# kernel.net
KiCad netlist of a schematic drawn in Altium Designer
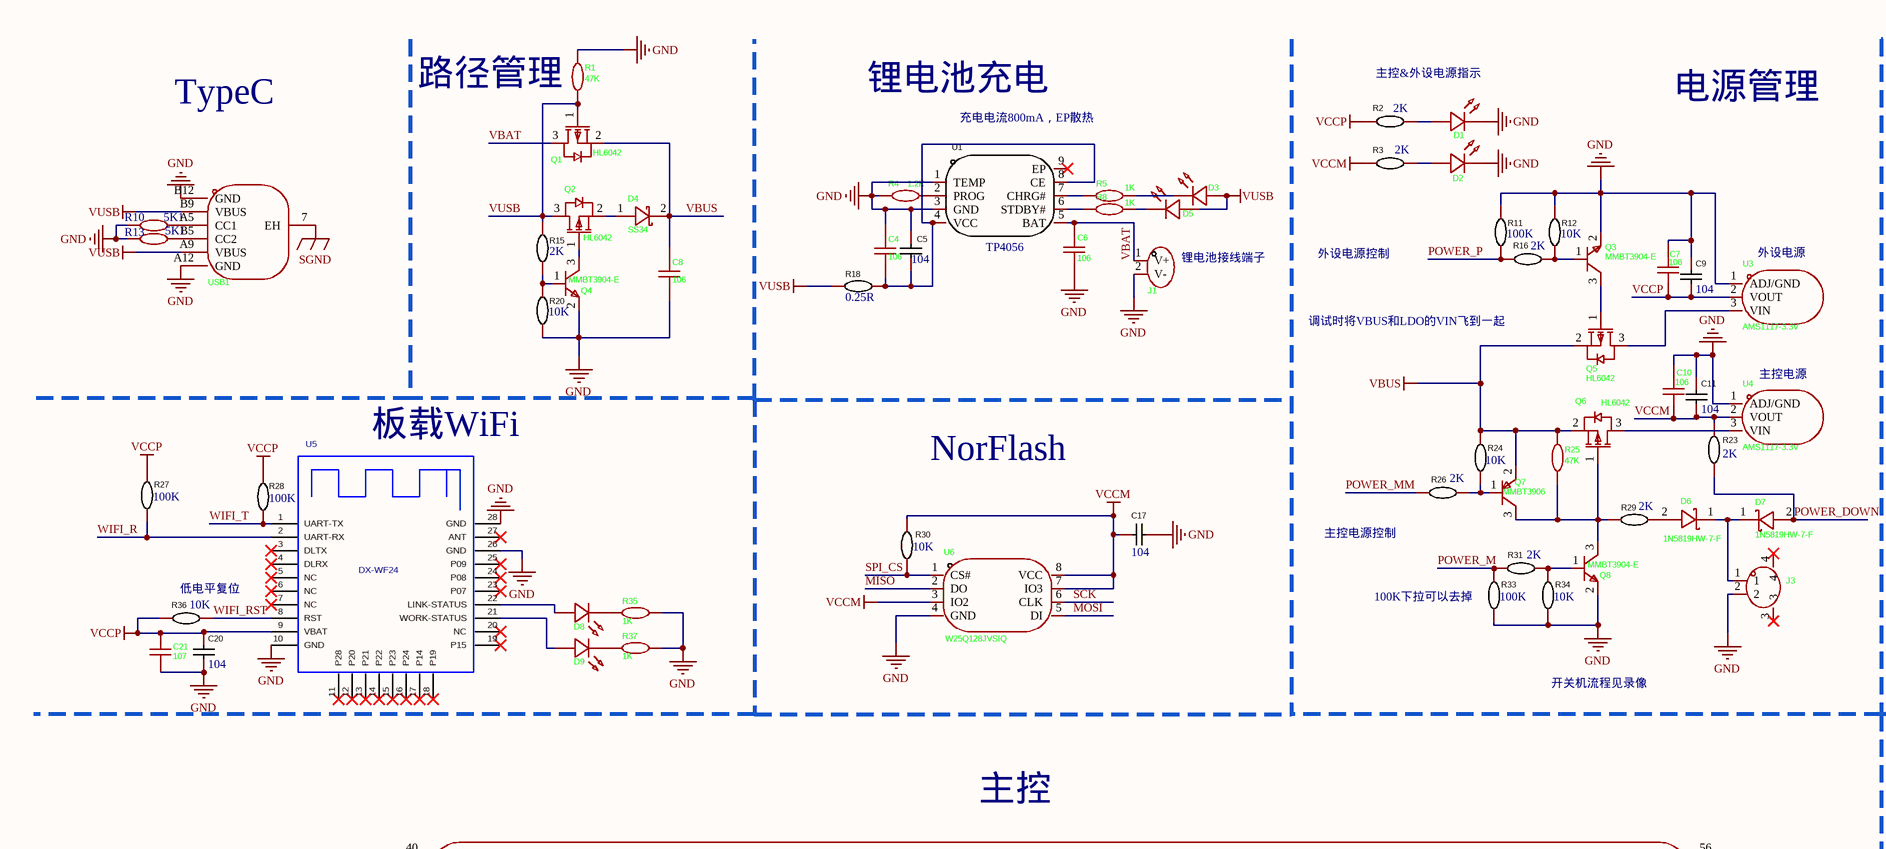
[diagram p0: kernel.SchDoc, top left]
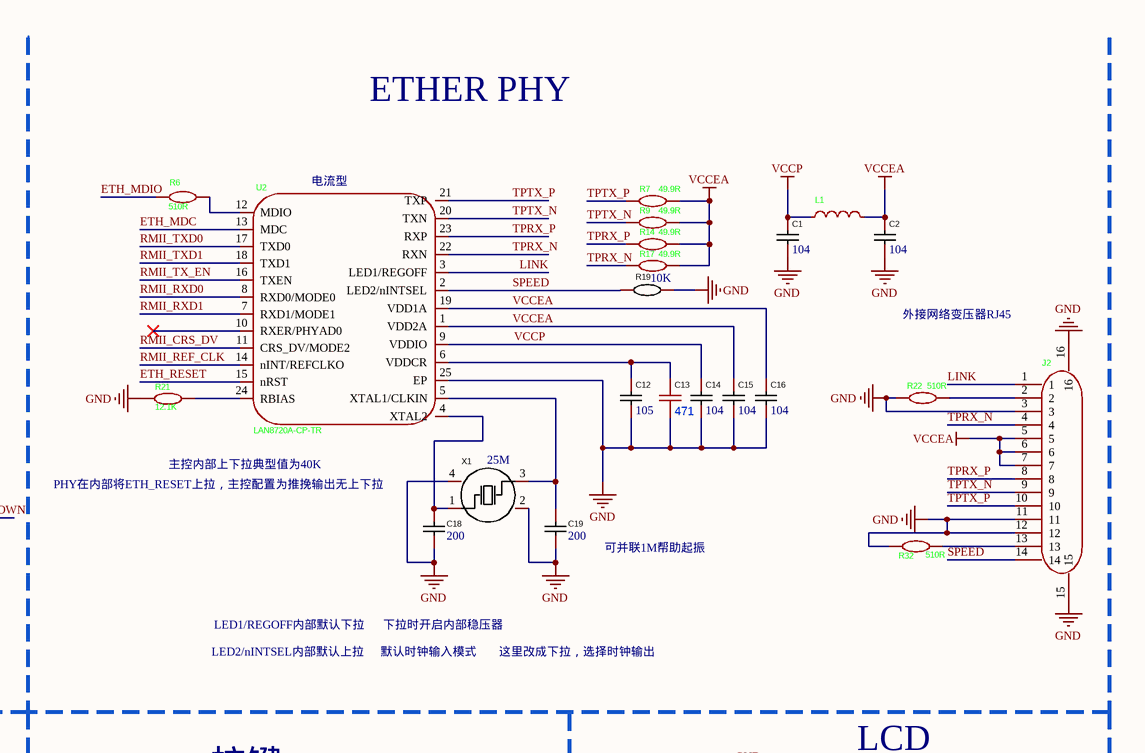
[diagram p1: kernel.SchDoc, top right]
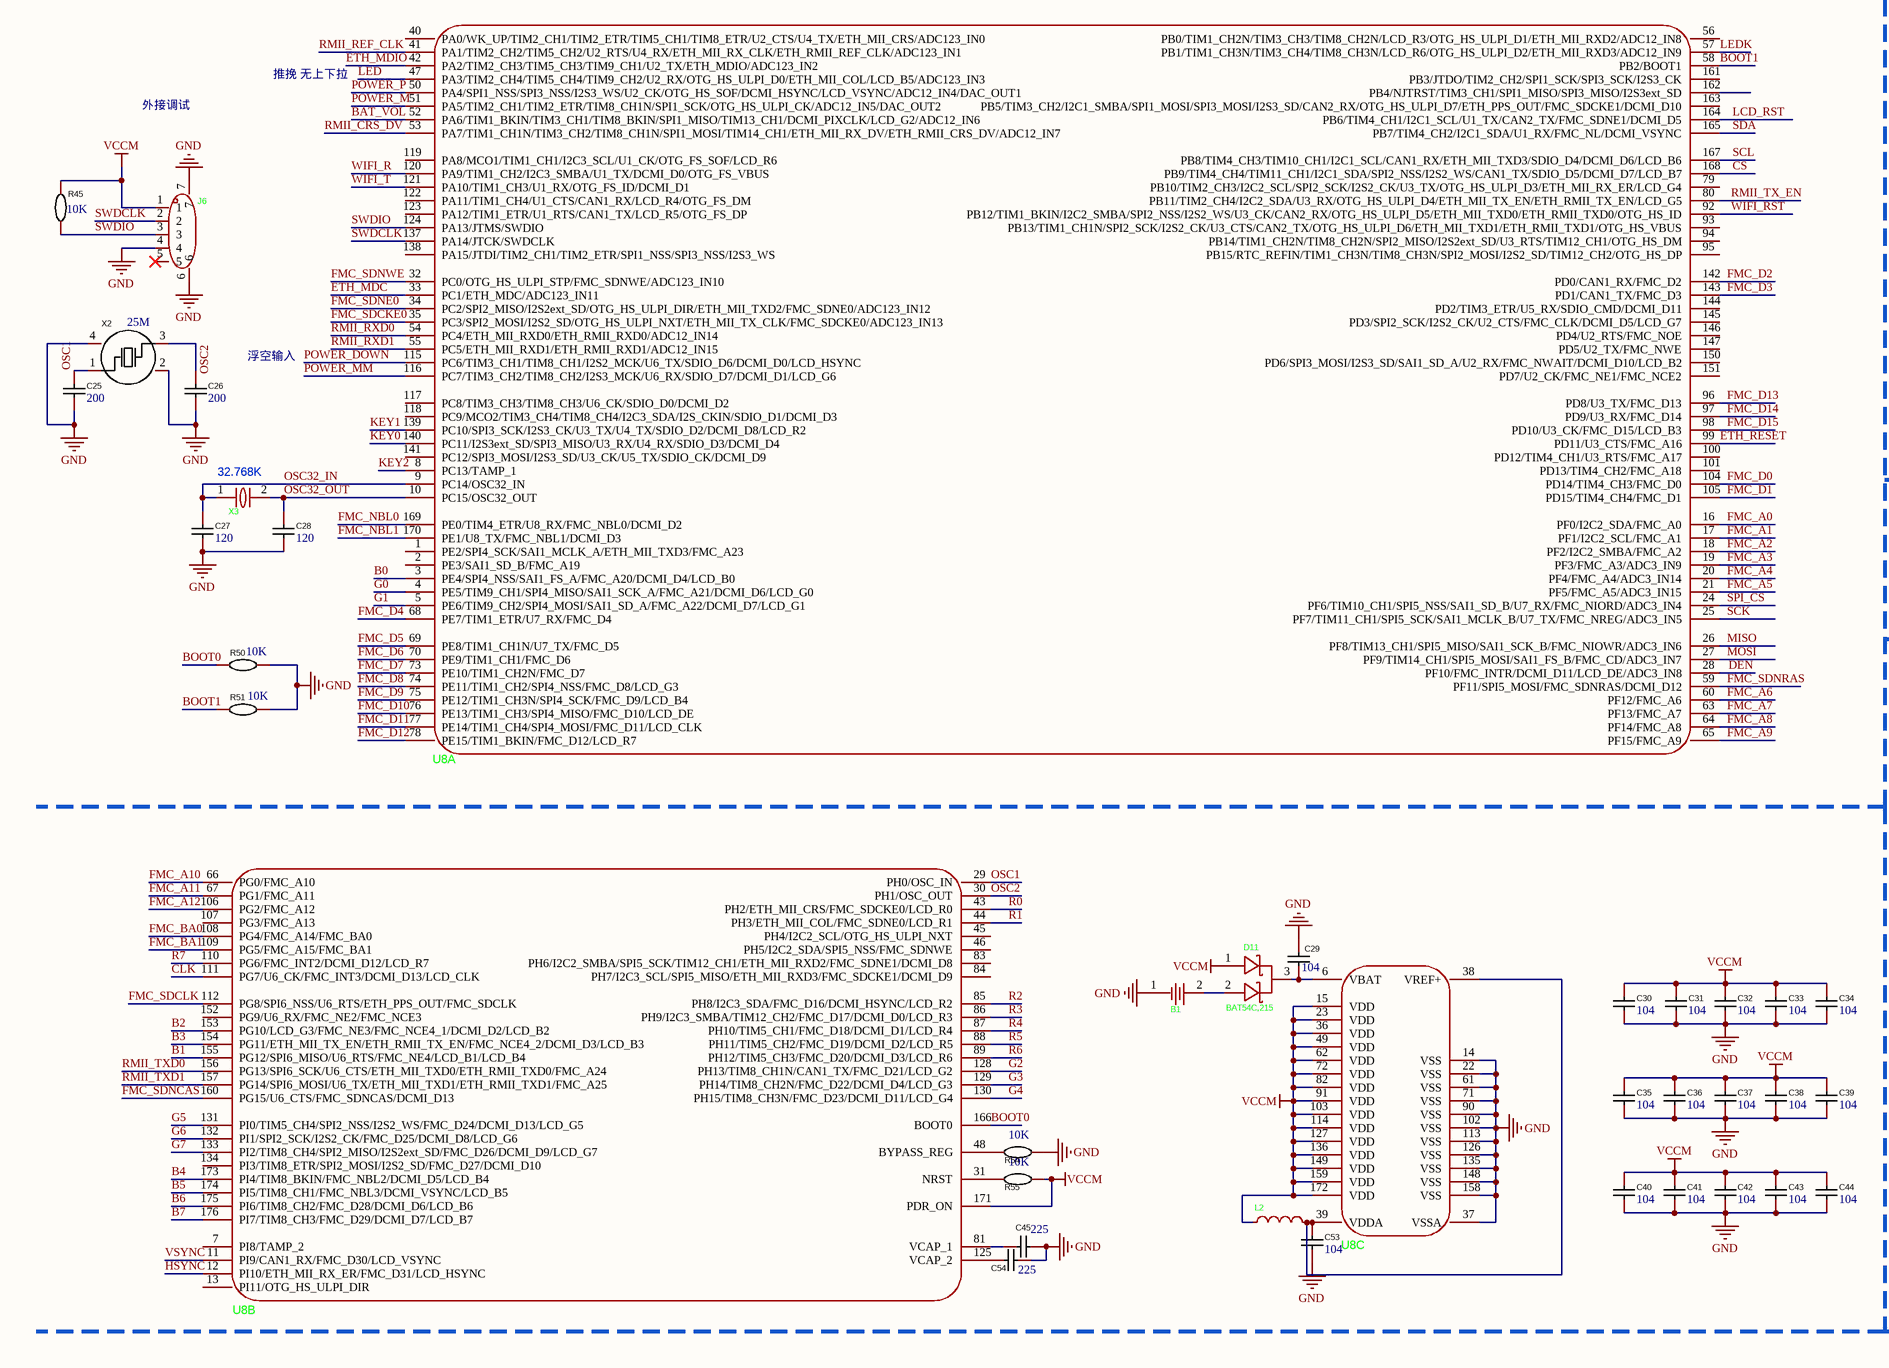
[diagram p2: kernel.SchDoc, bottom left]
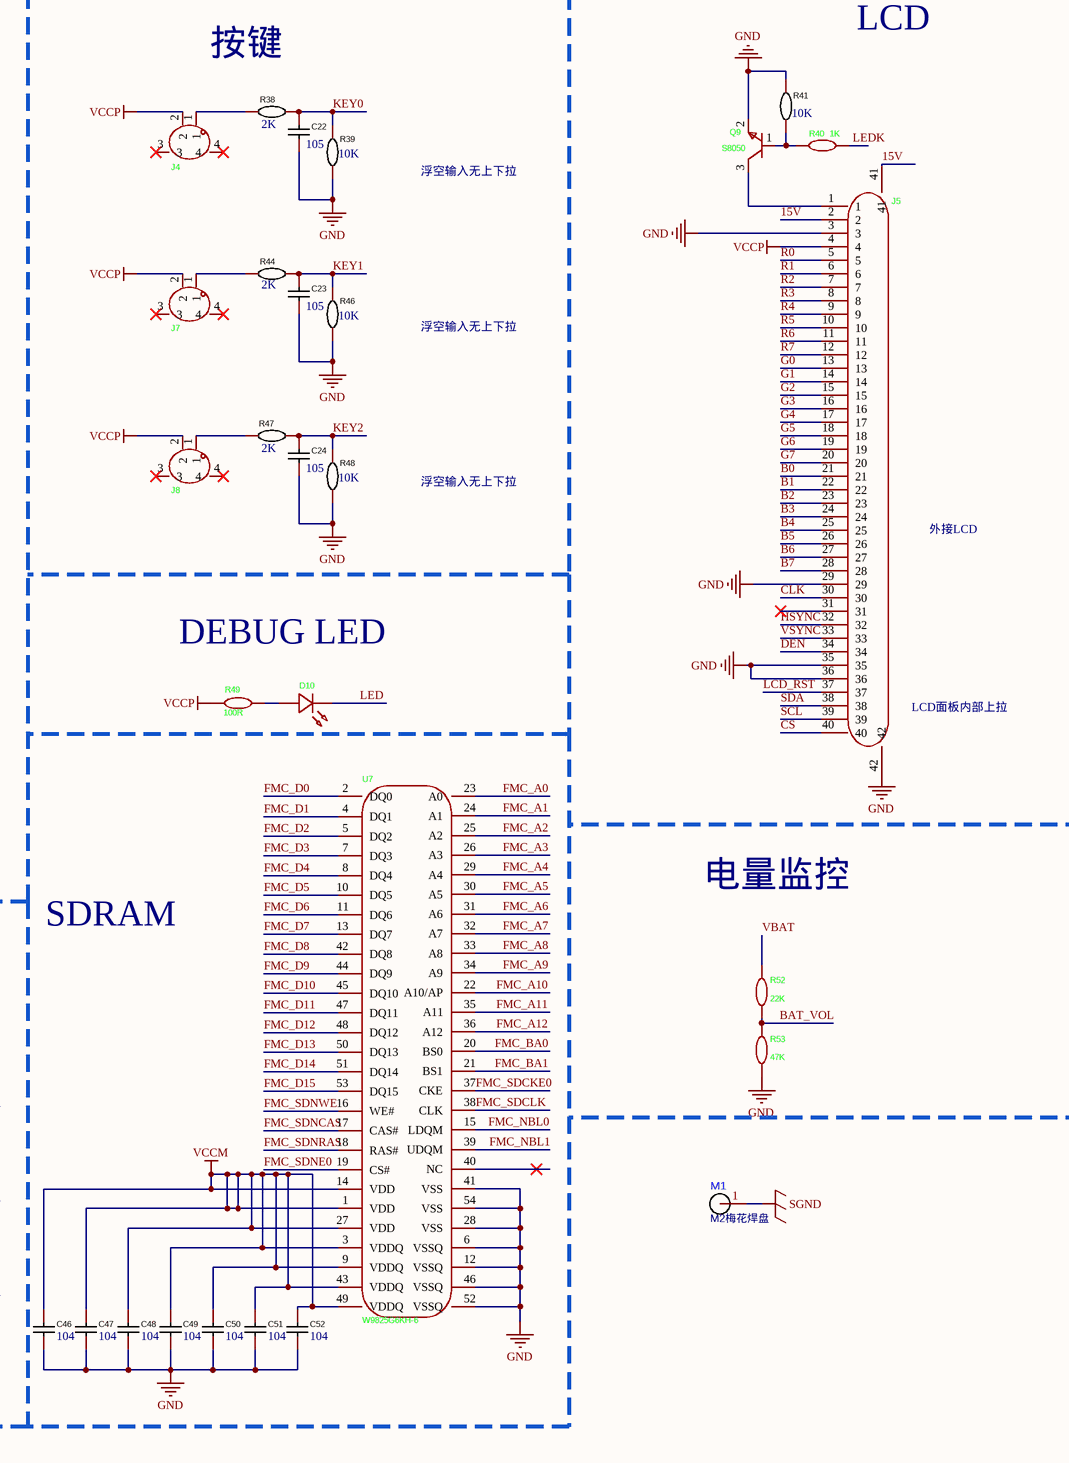
[diagram p3: kernel.SchDoc, bottom right]

(export (version "E")
  (design (tool "Eeschema 10.0.6"))
  (components
    (comp (ref "B1")
      (value "BS-02-A1AJ010")
      (footprint "BAT-TH_BS-02-A1AJ010")
      (description "CR2032电池座")
      (fields (field (name "MANUFACTURER") "MYOUNG(美阳)"))
      (libsource (lib "altium-import") (part "root_0_BS-02-A1AJ010_"))
    )
    (comp (ref "C1")
      (value "104")
      (footprint "0402_C")
      (description "电容100nf")
      (fields (field (name "MANUFACTURER") "FH(风华)") (field (name "MANUFACTURER PART") "0402CG200J500NT"))
      (libsource (lib "altium-import") (part "root_1_0402C_104_"))
    )
    (comp (ref "C2")
      (value "104")
      (footprint "0402_C")
      (description "电容100nf")
      (fields (field (name "MANUFACTURER") "FH(风华)") (field (name "MANUFACTURER PART") "0402CG200J500NT"))
      (libsource (lib "altium-import") (part "root_1_0402C_104_"))
    )
    (comp (ref "C4")
      (value "106")
      (footprint "0603_C")
      (description "电容10uf")
      (fields
        (field (name "MANUFACTURER") "HRE(芯声)")
        (field (name "MANUFACTURER PART") "CGA0603X5R106K100JT")
      )
      (libsource (lib "kernel") (part "CGA0603X5R106K100JT"))
    )
    (comp (ref "C5")
      (value "104")
      (footprint "0402_C")
      (description "电容100nf")
      (fields (field (name "MANUFACTURER") "FH(风华)") (field (name "MANUFACTURER PART") "0402CG200J500NT"))
      (libsource (lib "kernel") (part "0402C_104"))
    )
    (comp (ref "C6")
      (value "106")
      (footprint "0603_C")
      (description "电容10uf")
      (fields
        (field (name "MANUFACTURER") "HRE(芯声)")
        (field (name "MANUFACTURER PART") "CGA0603X5R106K100JT")
      )
      (libsource (lib "kernel") (part "CGA0603X5R106K100JT"))
    )
    (comp (ref "C7")
      (value "106")
      (footprint "0603_C")
      (description "电容10uf")
      (fields
        (field (name "MANUFACTURER") "HRE(芯声)")
        (field (name "MANUFACTURER PART") "CGA0603X5R106K100JT")
      )
      (libsource (lib "kernel") (part "CGA0603X5R106K100JT"))
    )
    (comp (ref "C8")
      (value "106")
      (footprint "0603_C")
      (description "电容10uf")
      (fields
        (field (name "MANUFACTURER") "HRE(芯声)")
        (field (name "MANUFACTURER PART") "CGA0603X5R106K100JT")
      )
      (libsource (lib "kernel") (part "CGA0603X5R106K100JT"))
    )
    (comp (ref "C9")
      (value "104")
      (footprint "0402_C")
      (description "电容100nf")
      (fields (field (name "MANUFACTURER") "FH(风华)") (field (name "MANUFACTURER PART") "0402CG200J500NT"))
      (libsource (lib "altium-import") (part "root_1_0402C_104_"))
    )
    (comp (ref "C10")
      (value "106")
      (footprint "0603_C")
      (description "电容10uf")
      (fields
        (field (name "MANUFACTURER") "HRE(芯声)")
        (field (name "MANUFACTURER PART") "CGA0603X5R106K100JT")
      )
      (libsource (lib "kernel") (part "CGA0603X5R106K100JT"))
    )
    (comp (ref "C11")
      (value "104")
      (footprint "0402_C")
      (description "电容100nf")
      (fields (field (name "MANUFACTURER") "FH(风华)") (field (name "MANUFACTURER PART") "0402CG200J500NT"))
      (libsource (lib "altium-import") (part "root_1_0402C_104_"))
    )
    (comp (ref "C12")
      (value "105")
      (footprint "0402_C")
      (description "电容1uf")
      (fields (field (name "MANUFACTURER") "FH(风华)") (field (name "MANUFACTURER PART") "0402CG200J500NT"))
      (libsource (lib "altium-import") (part "root_1_0402C_105_"))
    )
    (comp (ref "C13")
      (value "471")
      (footprint "0402_C")
      (description "电容470pf")
      (fields (field (name "MANUFACTURER") "FH(风华)") (field (name "MANUFACTURER PART") "0402B471K500NT"))
      (libsource (lib "altium-import") (part "root_1_0402B471K500NT_"))
    )
    (comp (ref "C14")
      (value "104")
      (footprint "0402_C")
      (description "电容100nf")
      (fields (field (name "MANUFACTURER") "FH(风华)") (field (name "MANUFACTURER PART") "0402CG200J500NT"))
      (libsource (lib "altium-import") (part "root_1_0402C_104_"))
    )
    (comp (ref "C15")
      (value "104")
      (footprint "0402_C")
      (description "电容100nf")
      (fields (field (name "MANUFACTURER") "FH(风华)") (field (name "MANUFACTURER PART") "0402CG200J500NT"))
      (libsource (lib "altium-import") (part "root_1_0402C_104_"))
    )
    (comp (ref "C16")
      (value "104")
      (footprint "0402_C")
      (description "电容100nf")
      (fields (field (name "MANUFACTURER") "FH(风华)") (field (name "MANUFACTURER PART") "0402CG200J500NT"))
      (libsource (lib "altium-import") (part "root_1_0402C_104_"))
    )
    (comp (ref "C17")
      (value "104")
      (footprint "0402_C")
      (description "电容100nf")
      (fields (field (name "MANUFACTURER") "FH(风华)") (field (name "MANUFACTURER PART") "0402CG200J500NT"))
      (libsource (lib "altium-import") (part "root_0_0402C_104_"))
    )
    (comp (ref "C18")
      (value "200")
      (footprint "0402_C")
      (description "电容20pf")
      (fields (field (name "MANUFACTURER") "FH(风华)") (field (name "MANUFACTURER PART") "0402CG200J500NT"))
      (libsource (lib "altium-import") (part "root_3_0402C_200_"))
    )
    (comp (ref "C19")
      (value "200")
      (footprint "0402_C")
      (description "电容20pf")
      (fields (field (name "MANUFACTURER") "FH(风华)") (field (name "MANUFACTURER PART") "0402CG200J500NT"))
      (libsource (lib "altium-import") (part "root_3_0402C_200_"))
    )
    (comp (ref "C20")
      (value "104")
      (footprint "0402_C")
      (description "电容100nf")
      (fields (field (name "MANUFACTURER") "FH(风华)") (field (name "MANUFACTURER PART") "0402CG200J500NT"))
      (libsource (lib "altium-import") (part "root_1_0402C_104_"))
    )
    (comp (ref "C21")
      (value "107")
      (footprint "1206_C")
      (description "电容100uf")
      (fields
        (field (name "MANUFACTURER") "SAMSUNG(三星)")
        (field (name "MANUFACTURER PART") "CL31A107MQHNNNE")
      )
      (libsource (lib "Schlib1") (part "CL31A107MQHNNNE"))
    )
    (comp (ref "C22")
      (value "105")
      (footprint "0402_C")
      (description "电容1uf")
      (fields (field (name "MANUFACTURER") "FH(风华)") (field (name "MANUFACTURER PART") "0402CG200J500NT"))
      (libsource (lib "altium-import") (part "root_1_0402C_105_"))
    )
    (comp (ref "C23")
      (value "105")
      (footprint "0402_C")
      (description "电容1uf")
      (fields (field (name "MANUFACTURER") "FH(风华)") (field (name "MANUFACTURER PART") "0402CG200J500NT"))
      (libsource (lib "altium-import") (part "root_1_0402C_105_"))
    )
    (comp (ref "C24")
      (value "105")
      (footprint "0402_C")
      (description "电容1uf")
      (fields (field (name "MANUFACTURER") "FH(风华)") (field (name "MANUFACTURER PART") "0402CG200J500NT"))
      (libsource (lib "altium-import") (part "root_1_0402C_105_"))
    )
    (comp (ref "C25")
      (value "200")
      (footprint "0402_C")
      (description "电容20pf")
      (fields (field (name "MANUFACTURER") "FH(风华)") (field (name "MANUFACTURER PART") "0402CG200J500NT"))
      (libsource (lib "altium-import") (part "root_3_0402C_200_"))
    )
    (comp (ref "C26")
      (value "200")
      (footprint "0402_C")
      (description "电容20pf")
      (fields (field (name "MANUFACTURER") "FH(风华)") (field (name "MANUFACTURER PART") "0402CG200J500NT"))
      (libsource (lib "altium-import") (part "root_3_0402C_200_"))
    )
    (comp (ref "C27")
      (value "120")
      (footprint "0402_C")
      (description "电容12pf")
      (fields (field (name "MANUFACTURER") "FH(风华)") (field (name "MANUFACTURER PART") "0402CG200J500NT"))
      (libsource (lib "altium-import") (part "root_1_0402C_120_"))
    )
    (comp (ref "C28")
      (value "120")
      (footprint "0402_C")
      (description "电容12pf")
      (fields (field (name "MANUFACTURER") "FH(风华)") (field (name "MANUFACTURER PART") "0402CG200J500NT"))
      (libsource (lib "altium-import") (part "root_1_0402C_120_"))
    )
    (comp (ref "C29")
      (value "104")
      (footprint "0402_C")
      (description "电容")
      (fields (field (name "MANUFACTURER") "FH(风华)") (field (name "MANUFACTURER PART") "0402CG200J500NT"))
      (libsource (lib "altium-import") (part "root_1_0402C_"))
    )
    (comp (ref "C30")
      (value "104")
      (footprint "0402_C")
      (description "电容")
      (fields (field (name "MANUFACTURER") "FH(风华)") (field (name "MANUFACTURER PART") "0402CG200J500NT"))
      (libsource (lib "altium-import") (part "root_1_0402C_"))
    )
    (comp (ref "C31")
      (value "104")
      (footprint "0402_C")
      (description "电容")
      (fields (field (name "MANUFACTURER") "FH(风华)") (field (name "MANUFACTURER PART") "0402CG200J500NT"))
      (libsource (lib "altium-import") (part "root_1_0402C_"))
    )
    (comp (ref "C32")
      (value "104")
      (footprint "0402_C")
      (description "电容")
      (fields (field (name "MANUFACTURER") "FH(风华)") (field (name "MANUFACTURER PART") "0402CG200J500NT"))
      (libsource (lib "altium-import") (part "root_1_0402C_"))
    )
    (comp (ref "C33")
      (value "104")
      (footprint "0402_C")
      (description "电容")
      (fields (field (name "MANUFACTURER") "FH(风华)") (field (name "MANUFACTURER PART") "0402CG200J500NT"))
      (libsource (lib "altium-import") (part "root_1_0402C_"))
    )
    (comp (ref "C34")
      (value "104")
      (footprint "0402_C")
      (description "电容")
      (fields (field (name "MANUFACTURER") "FH(风华)") (field (name "MANUFACTURER PART") "0402CG200J500NT"))
      (libsource (lib "altium-import") (part "root_1_0402C_"))
    )
    (comp (ref "C35")
      (value "104")
      (footprint "0402_C")
      (description "电容")
      (fields (field (name "MANUFACTURER") "FH(风华)") (field (name "MANUFACTURER PART") "0402CG200J500NT"))
      (libsource (lib "altium-import") (part "root_1_0402C_"))
    )
    (comp (ref "C36")
      (value "104")
      (footprint "0402_C")
      (description "电容")
      (fields (field (name "MANUFACTURER") "FH(风华)") (field (name "MANUFACTURER PART") "0402CG200J500NT"))
      (libsource (lib "altium-import") (part "root_1_0402C_"))
    )
    (comp (ref "C37")
      (value "104")
      (footprint "0402_C")
      (description "电容")
      (fields (field (name "MANUFACTURER") "FH(风华)") (field (name "MANUFACTURER PART") "0402CG200J500NT"))
      (libsource (lib "altium-import") (part "root_1_0402C_"))
    )
    (comp (ref "C38")
      (value "104")
      (footprint "0402_C")
      (description "电容")
      (fields (field (name "MANUFACTURER") "FH(风华)") (field (name "MANUFACTURER PART") "0402CG200J500NT"))
      (libsource (lib "altium-import") (part "root_1_0402C_"))
    )
    (comp (ref "C39")
      (value "104")
      (footprint "0402_C")
      (description "电容")
      (fields (field (name "MANUFACTURER") "FH(风华)") (field (name "MANUFACTURER PART") "0402CG200J500NT"))
      (libsource (lib "altium-import") (part "root_1_0402C_"))
    )
    (comp (ref "C40")
      (value "104")
      (footprint "0402_C")
      (description "电容")
      (fields (field (name "MANUFACTURER") "FH(风华)") (field (name "MANUFACTURER PART") "0402CG200J500NT"))
      (libsource (lib "altium-import") (part "root_1_0402C_"))
    )
    (comp (ref "C41")
      (value "104")
      (footprint "0402_C")
      (description "电容")
      (fields (field (name "MANUFACTURER") "FH(风华)") (field (name "MANUFACTURER PART") "0402CG200J500NT"))
      (libsource (lib "altium-import") (part "root_1_0402C_"))
    )
    (comp (ref "C42")
      (value "104")
      (footprint "0402_C")
      (description "电容")
      (fields (field (name "MANUFACTURER") "FH(风华)") (field (name "MANUFACTURER PART") "0402CG200J500NT"))
      (libsource (lib "altium-import") (part "root_1_0402C_"))
    )
    (comp (ref "C43")
      (value "104")
      (footprint "0402_C")
      (description "电容")
      (fields (field (name "MANUFACTURER") "FH(风华)") (field (name "MANUFACTURER PART") "0402CG200J500NT"))
      (libsource (lib "altium-import") (part "root_1_0402C_"))
    )
    (comp (ref "C44")
      (value "104")
      (footprint "0402_C")
      (description "电容")
      (fields (field (name "MANUFACTURER") "FH(风华)") (field (name "MANUFACTURER PART") "0402CG200J500NT"))
      (libsource (lib "altium-import") (part "root_1_0402C_"))
    )
    (comp (ref "C45")
      (value "225")
      (footprint "0402_C")
      (description "电容2.2uf")
      (fields (field (name "MANUFACTURER") "FH(风华)") (field (name "MANUFACTURER PART") "0402CG200J500NT"))
      (libsource (lib "kernel") (part "0402C_225"))
    )
    (comp (ref "C46")
      (value "104")
      (footprint "0402_C")
      (description "电容")
      (fields (field (name "MANUFACTURER") "FH(风华)") (field (name "MANUFACTURER PART") "0402CG200J500NT"))
      (libsource (lib "altium-import") (part "root_1_0402C_"))
    )
    (comp (ref "C47")
      (value "104")
      (footprint "0402_C")
      (description "电容")
      (fields (field (name "MANUFACTURER") "FH(风华)") (field (name "MANUFACTURER PART") "0402CG200J500NT"))
      (libsource (lib "altium-import") (part "root_1_0402C_"))
    )
    (comp (ref "C48")
      (value "104")
      (footprint "0402_C")
      (description "电容")
      (fields (field (name "MANUFACTURER") "FH(风华)") (field (name "MANUFACTURER PART") "0402CG200J500NT"))
      (libsource (lib "altium-import") (part "root_1_0402C_"))
    )
    (comp (ref "C49")
      (value "104")
      (footprint "0402_C")
      (description "电容")
      (fields (field (name "MANUFACTURER") "FH(风华)") (field (name "MANUFACTURER PART") "0402CG200J500NT"))
      (libsource (lib "altium-import") (part "root_1_0402C_"))
    )
    (comp (ref "C50")
      (value "104")
      (footprint "0402_C")
      (description "电容")
      (fields (field (name "MANUFACTURER") "FH(风华)") (field (name "MANUFACTURER PART") "0402CG200J500NT"))
      (libsource (lib "altium-import") (part "root_1_0402C_"))
    )
    (comp (ref "C51")
      (value "104")
      (footprint "0402_C")
      (description "电容")
      (fields (field (name "MANUFACTURER") "FH(风华)") (field (name "MANUFACTURER PART") "0402CG200J500NT"))
      (libsource (lib "altium-import") (part "root_1_0402C_"))
    )
    (comp (ref "C52")
      (value "104")
      (footprint "0402_C")
      (description "电容")
      (fields (field (name "MANUFACTURER") "FH(风华)") (field (name "MANUFACTURER PART") "0402CG200J500NT"))
      (libsource (lib "altium-import") (part "root_1_0402C_"))
    )
    (comp (ref "C53")
      (value "104")
      (footprint "0402_C")
      (description "电容")
      (fields (field (name "MANUFACTURER") "FH(风华)") (field (name "MANUFACTURER PART") "0402CG200J500NT"))
      (libsource (lib "altium-import") (part "root_1_0402C_"))
    )
    (comp (ref "C54")
      (value "225")
      (footprint "0402_C")
      (description "电容2.2uf")
      (fields (field (name "MANUFACTURER") "FH(风华)") (field (name "MANUFACTURER PART") "0402CG200J500NT"))
      (libsource (lib "kernel") (part "0402C_225"))
    )
    (comp (ref "D1")
      (value "XL-1005SYGC")
      (footprint "LED-SMD_L1.1-W0.6-FD")
      (description "LED黄绿")
      (fields (field (name "MANUFACTURER") "XINGLIGHT(成兴光)"))
      (libsource (lib "altium-import") (part "root_0_XL-1005SYGC_C22470306_"))
    )
    (comp (ref "D2")
      (value "XL-1005SYGC")
      (footprint "LED-SMD_L1.1-W0.6-FD")
      (description "LED黄绿")
      (fields (field (name "MANUFACTURER") "XINGLIGHT(成兴光)"))
      (libsource (lib "altium-import") (part "root_0_XL-1005SYGC_C22470306_"))
    )
    (comp (ref "D3")
      (value "XL-1005SYGC")
      (footprint "LED-SMD_L1.1-W0.6-FD")
      (description "LED黄绿")
      (fields (field (name "MANUFACTURER") "XINGLIGHT(成兴光)"))
      (libsource (lib "kernel") (part "XL-1005SYGC_C22470306"))
    )
    (comp (ref "D4")
      (value "SS34")
      (footprint "SMA_L4.3-W2.6-LS5.0-FD")
      (fields (field (name "MANUFACTURER") "R+O(宏嘉诚)"))
      (libsource (lib "power") (part "SS34"))
    )
    (comp (ref "D5")
      (value "XL-1005SURC")
      (footprint "LED0402-RD")
      (description "LED红")
      (fields (field (name "MANUFACTURER") "XINGLIGHT(成兴光)"))
      (libsource (lib "kernel") (part "XL-1005SURC_C25503345"))
    )
    (comp (ref "D6")
      (value "1N5819HW-7-F")
      (footprint "SOD-123_L2.7-W1.6-LS3.7-RD")
      (description "肖特基二极管")
      (fields (field (name "MANUFACTURER") "DIODES(美台)"))
      (libsource (lib "power") (part "1N5819HW-7-F"))
    )
    (comp (ref "D7")
      (value "1N5819HW-7-F")
      (footprint "SOD-123_L2.7-W1.6-LS3.7-RD")
      (description "肖特基二极管")
      (fields (field (name "MANUFACTURER") "DIODES(美台)"))
      (libsource (lib "power") (part "1N5819HW-7-F"))
    )
    (comp (ref "D8")
      (value "XL-1005SURC")
      (footprint "LED0402-RD")
      (description "LED红")
      (fields (field (name "MANUFACTURER") "XINGLIGHT(成兴光)"))
      (libsource (lib "Schlib1") (part "XL-1005SURC_C25503345"))
    )
    (comp (ref "D9")
      (value "XL-1005SURC")
      (footprint "LED0402-RD")
      (description "LED红")
      (fields (field (name "MANUFACTURER") "XINGLIGHT(成兴光)"))
      (libsource (lib "Schlib1") (part "XL-1005SURC_C25503345"))
    )
    (comp (ref "D10")
      (value "XL-1005UOC")
      (footprint "LED0402-RD_ORANGE")
      (description "LED橙")
      (fields (field (name "MANUFACTURER") "XINGLIGHT(成兴光)"))
      (libsource (lib "altium-import") (part "root_2_XL-1005UOC_"))
    )
    (comp (ref "D11")
      (value "BAT54C,215")
      (footprint "SOT-23-3_L2.9-W1.6-P1.90-LS2.8-BR")
      (description "共阴二极管")
      (fields (field (name "MANUFACTURER") "Nexperia(安世)"))
      (libsource (lib "altium-import") (part "root_0_BAT54C,215_"))
    )
    (comp (ref "J1")
      (value "ZX-XH2.54-2PZZ")
      (footprint "CONN-TH_2P-P2.50_HX25003-2A")
      (fields (field (name "MANUFACTURER") "Megastar(兆星)"))
      (libsource (lib "power") (part "ZX-XH2.54-2PZZ"))
    )
    (comp (ref "J2")
      (value "AFC01-S14FCA-00")
      (footprint "FPC-SMD_AFC01-S14FCA-00")
      (description "FPC")
      (fields (field (name "MANUFACTURER") "JS(钜硕电子)"))
      (libsource (lib "altium-import") (part "root_0_AFC01-S14FCA-00_"))
    )
    (comp (ref "J3")
      (value "WAFER-SH1.0-2PWB")
      (footprint "CONN-SMD_2P-P1.00_XUNPU_WAFER-SH1.0-2PWB")
      (description "按键连接器")
      (fields (field (name "MANUFACTURER") "XUNPU(讯普)"))
      (libsource (lib "kernel") (part "WAFER-SH1.0-2PWB"))
    )
    (comp (ref "J4")
      (value "WAFER-SH1.0-2PWB")
      (footprint "CONN-SMD_2P-P1.00_XUNPU_WAFER-SH1.0-2PWB")
      (description "按键连接器")
      (fields (field (name "MANUFACTURER") "XUNPU(讯普)"))
      (libsource (lib "kernel") (part "WAFER-SH1.0-2PWB"))
    )
    (comp (ref "J5")
      (value "AFC01-S40FCA-00")
      (footprint "FPC-SMD_AFC01-S40FCA-00")
      (description "FPC")
      (fields (field (name "MANUFACTURER") "JS(钜硕电子)"))
      (libsource (lib "Schlib1") (part "AFC01-S40FCA-00"))
    )
    (comp (ref "J6")
      (value "AFC01-S05FCA-00")
      (footprint "FPC-SMD_AFC01-S05FCA-00")
      (description "DEBUG")
      (fields (field (name "MANUFACTURER") "JS(钜硕电子)"))
      (libsource (lib "altium-import") (part "root_0_AFC01-S05FCA-00_"))
    )
    (comp (ref "J7")
      (value "WAFER-SH1.0-2PWB")
      (footprint "CONN-SMD_2P-P1.00_XUNPU_WAFER-SH1.0-2PWB")
      (description "按键连接器")
      (fields (field (name "MANUFACTURER") "XUNPU(讯普)"))
      (libsource (lib "kernel") (part "WAFER-SH1.0-2PWB"))
    )
    (comp (ref "J8")
      (value "WAFER-SH1.0-2PWB")
      (footprint "CONN-SMD_2P-P1.00_XUNPU_WAFER-SH1.0-2PWB")
      (description "按键连接器")
      (fields (field (name "MANUFACTURER") "XUNPU(讯普)"))
      (libsource (lib "kernel") (part "WAFER-SH1.0-2PWB"))
    )
    (comp (ref "L1")
      (value "BLM21PG221SN1D")
      (footprint "0805_L")
      (description "磁珠")
      (fields (field (name "MANUFACTURER") "muRata(村田)") (field (name "TOLERANCE") "±25%"))
      (libsource (lib "altium-import") (part "root_0_BLM21PG221SN1D_"))
    )
    (comp (ref "L2")
      (value "BLM15AG100SN1D")
      (footprint "0402_L")
      (fields (field (name "MANUFACTURER") "muRata(村田)"))
      (libsource (lib "kernel") (part "BLM15AG100SN1D"))
    )
    (comp (ref "M1")
      (value "M2梅花焊盘")
      (footprint "PCBComponent_1 - duplicate")
      (libsource (lib "kernel") (part "M2梅花焊盘"))
    )
    (comp (ref "Q1")
      (value "HL6042")
      (footprint "SOT-23-3_L2.9-W1.4-P1.90-LS2.5-BR")
      (fields (field (name "MANUFACTURER") "R+O(宏嘉诚)"))
      (libsource (lib "power") (part "HL6042"))
    )
    (comp (ref "Q2")
      (value "HL6042")
      (footprint "SOT-23-3_L2.9-W1.4-P1.90-LS2.5-BR")
      (fields (field (name "MANUFACTURER") "R+O(宏嘉诚)"))
      (libsource (lib "power") (part "HL6042"))
    )
    (comp (ref "Q3")
      (value "MMBT3904-E")
      (footprint "SOT-23-3_L2.9-W1.4-P1.90-LS2.5-BR")
      (description "NPN")
      (fields (field (name "MANUFACTURER") "MDD(辰达半导体)"))
      (libsource (lib "power") (part "MMBT3904-E"))
    )
    (comp (ref "Q4")
      (value "MMBT3904-E")
      (footprint "SOT-23-3_L2.9-W1.4-P1.90-LS2.5-BR")
      (description "NPN")
      (fields (field (name "MANUFACTURER") "MDD(辰达半导体)"))
      (libsource (lib "power") (part "MMBT3904-E"))
    )
    (comp (ref "Q5")
      (value "HL6042")
      (footprint "SOT-23-3_L2.9-W1.4-P1.90-LS2.5-BR")
      (fields (field (name "MANUFACTURER") "R+O(宏嘉诚)"))
      (libsource (lib "power") (part "HL6042"))
    )
    (comp (ref "Q6")
      (value "HL6042")
      (footprint "SOT-23-3_L2.9-W1.4-P1.90-LS2.5-BR")
      (fields (field (name "MANUFACTURER") "R+O(宏嘉诚)"))
      (libsource (lib "power") (part "HL6042"))
    )
    (comp (ref "Q7")
      (value "MMBT3906")
      (footprint "SOT-23-3_L2.9-W1.3-P1.90-LS2.4-BR")
      (description "PNP")
      (fields (field (name "MANUFACTURER") "MDD(辰达半导体)"))
      (libsource (lib "power") (part "MMBT3906_C364311"))
    )
    (comp (ref "Q8")
      (value "MMBT3904-E")
      (footprint "SOT-23-3_L2.9-W1.4-P1.90-LS2.5-BR")
      (description "NPN")
      (fields (field (name "MANUFACTURER") "MDD(辰达半导体)"))
      (libsource (lib "power") (part "MMBT3904-E"))
    )
    (comp (ref "Q9")
      (value "S8050")
      (footprint "SOT-23-3_L3.0-W1.7-P0.95-LS2.9-BR")
      (description "NPN")
      (fields (field (name "MANUFACTURER") "MDD(辰达半导体)"))
      (libsource (lib "kernel") (part "S8050_C364312"))
    )
    (comp (ref "R1")
      (value "47K")
      (footprint "0402_R")
      (description "电阻47K")
      (fields
        (field (name "MANUFACTURER") "UNI-ROYAL(厚声)")
        (field (name "MANUFACTURER PART") "0402WGF4702TCE")
      )
      (libsource (lib "kernel") (part "0402WGF4702TCE"))
    )
    (comp (ref "R2")
      (value "2K")
      (footprint "0402_R")
      (description "电阻2K")
      (fields
        (field (name "MANUFACTURER") "UNI-ROYAL(厚声)")
        (field (name "MANUFACTURER PART") "0402WGF1002TCE")
      )
      (libsource (lib "kernel") (part "0402WGF2001TCE"))
    )
    (comp (ref "R3")
      (value "2K")
      (footprint "0402_R")
      (description "电阻2K")
      (fields
        (field (name "MANUFACTURER") "UNI-ROYAL(厚声)")
        (field (name "MANUFACTURER PART") "0402WGF1002TCE")
      )
      (libsource (lib "kernel") (part "0402WGF2001TCE"))
    )
    (comp (ref "R4")
      (value "1.2K")
      (footprint "0603_R")
      (description "电阻1.2K")
      (fields
        (field (name "MANUFACTURER") "UNI-ROYAL(厚声)")
        (field (name "MANUFACTURER PART") "0603WAF1201T5E")
      )
      (libsource (lib "kernel") (part "0603WAF1201T5E"))
    )
    (comp (ref "R5")
      (value "1K")
      (footprint "0402_R")
      (description "电阻1K")
      (fields
        (field (name "MANUFACTURER") "UNI-ROYAL(厚声)")
        (field (name "MANUFACTURER PART") "0402WGF1001TCE")
      )
      (libsource (lib "kernel") (part "0402WGF1001TCE"))
    )
    (comp (ref "R6")
      (value "510R")
      (footprint "0603_R")
      (description "电阻510R")
      (fields
        (field (name "MANUFACTURER") "UNI-ROYAL(厚声)")
        (field (name "MANUFACTURER PART") "0603WAF5100T5E")
      )
      (libsource (lib "altium-import") (part "root_0_0603WAF5100T5E_"))
    )
    (comp (ref "R7")
      (value "49.9R")
      (footprint "0603_R")
      (description "电阻49.9R")
      (fields
        (field (name "MANUFACTURER") "UNI-ROYAL(厚声)")
        (field (name "MANUFACTURER PART") "0603WAF499JT5E")
      )
      (libsource (lib "altium-import") (part "root_0_0603WAF499JT5E_"))
    )
    (comp (ref "R8")
      (value "1K")
      (footprint "0402_R")
      (description "电阻1K")
      (fields
        (field (name "MANUFACTURER") "UNI-ROYAL(厚声)")
        (field (name "MANUFACTURER PART") "0402WGF1001TCE")
      )
      (libsource (lib "kernel") (part "0402WGF1001TCE"))
    )
    (comp (ref "R9")
      (value "49.9R")
      (footprint "0603_R")
      (description "电阻49.9R")
      (fields
        (field (name "MANUFACTURER") "UNI-ROYAL(厚声)")
        (field (name "MANUFACTURER PART") "0603WAF499JT5E")
      )
      (libsource (lib "altium-import") (part "root_0_0603WAF499JT5E_"))
    )
    (comp (ref "R10")
      (value "5K1")
      (footprint "0402_R")
      (description "电阻5.1K")
      (libsource (lib "kernel") (part "0402WGF5101TCE"))
    )
    (comp (ref "R11")
      (value "100K")
      (footprint "0402_R")
      (description "电阻100K")
      (fields
        (field (name "MANUFACTURER") "UNI-ROYAL(厚声)")
        (field (name "MANUFACTURER PART") "0402WGF1002TCE")
      )
      (libsource (lib "kernel") (part "0402WGF1003TCE"))
    )
    (comp (ref "R12")
      (value "10K")
      (footprint "0402_R")
      (description "电阻10K")
      (fields
        (field (name "MANUFACTURER") "UNI-ROYAL(厚声)")
        (field (name "MANUFACTURER PART") "0402WGF1002TCE")
      )
      (libsource (lib "altium-import") (part "root_1_0402WGF1002TCE_"))
    )
    (comp (ref "R13")
      (value "5K1")
      (footprint "0402_R")
      (description "电阻5.1K")
      (libsource (lib "kernel") (part "0402WGF5101TCE"))
    )
    (comp (ref "R14")
      (value "49.9R")
      (footprint "0603_R")
      (description "电阻49.9R")
      (fields
        (field (name "MANUFACTURER") "UNI-ROYAL(厚声)")
        (field (name "MANUFACTURER PART") "0603WAF499JT5E")
      )
      (libsource (lib "altium-import") (part "root_0_0603WAF499JT5E_"))
    )
    (comp (ref "R15")
      (value "2K")
      (footprint "0402_R")
      (description "电阻2K")
      (fields
        (field (name "MANUFACTURER") "UNI-ROYAL(厚声)")
        (field (name "MANUFACTURER PART") "0402WGF1002TCE")
      )
      (libsource (lib "kernel") (part "0402WGF2001TCE"))
    )
    (comp (ref "R16")
      (value "2K")
      (footprint "0402_R")
      (description "电阻2K")
      (fields
        (field (name "MANUFACTURER") "UNI-ROYAL(厚声)")
        (field (name "MANUFACTURER PART") "0402WGF1002TCE")
      )
      (libsource (lib "kernel") (part "0402WGF2001TCE"))
    )
    (comp (ref "R17")
      (value "49.9R")
      (footprint "0603_R")
      (description "电阻49.9R")
      (fields
        (field (name "MANUFACTURER") "UNI-ROYAL(厚声)")
        (field (name "MANUFACTURER PART") "0603WAF499JT5E")
      )
      (libsource (lib "altium-import") (part "root_0_0603WAF499JT5E_"))
    )
    (comp (ref "R18")
      (value "0.25R")
      (footprint "1206_R")
      (description "res")
      (fields
        (field (name "MANUFACTURER") "UNI-ROYAL(厚声)")
        (field (name "MANUFACTURER PART") "0402WGF1002TCE")
      )
      (libsource (lib "Schlib1") (part "0402WGF1002TCE"))
    )
    (comp (ref "R19")
      (value "10K")
      (footprint "0402_R")
      (description "电阻10K")
      (fields
        (field (name "MANUFACTURER") "UNI-ROYAL(厚声)")
        (field (name "MANUFACTURER PART") "0402WGF1002TCE")
      )
      (libsource (lib "altium-import") (part "root_0_0402WGF1002TCE_"))
    )
    (comp (ref "R20")
      (value "10K")
      (footprint "0402_R")
      (description "电阻10K")
      (fields
        (field (name "MANUFACTURER") "UNI-ROYAL(厚声)")
        (field (name "MANUFACTURER PART") "0402WGF1002TCE")
      )
      (libsource (lib "altium-import") (part "root_1_0402WGF1002TCE_"))
    )
    (comp (ref "R21")
      (value "12.1K")
      (footprint "0603_R")
      (description "电阻12.1K")
      (fields
        (field (name "MANUFACTURER") "UNI-ROYAL(厚声)")
        (field (name "MANUFACTURER PART") "0603WAF1212T5E")
      )
      (libsource (lib "altium-import") (part "root_0_0603WAF1212T5E_"))
    )
    (comp (ref "R22")
      (value "510R")
      (footprint "0603_R")
      (description "电阻510R")
      (fields
        (field (name "MANUFACTURER") "UNI-ROYAL(厚声)")
        (field (name "MANUFACTURER PART") "0603WAF5100T5E")
      )
      (libsource (lib "altium-import") (part "root_0_0603WAF5100T5E_"))
    )
    (comp (ref "R23")
      (value "2K")
      (footprint "0402_R")
      (description "电阻2K")
      (fields
        (field (name "MANUFACTURER") "UNI-ROYAL(厚声)")
        (field (name "MANUFACTURER PART") "0402WGF1002TCE")
      )
      (libsource (lib "kernel") (part "0402WGF2001TCE"))
    )
    (comp (ref "R24")
      (value "10K")
      (footprint "0402_R")
      (description "电阻10K")
      (fields
        (field (name "MANUFACTURER") "UNI-ROYAL(厚声)")
        (field (name "MANUFACTURER PART") "0402WGF1002TCE")
      )
      (libsource (lib "altium-import") (part "root_1_0402WGF1002TCE_"))
    )
    (comp (ref "R25")
      (value "47K")
      (footprint "0402_R")
      (description "电阻47K")
      (fields
        (field (name "MANUFACTURER") "UNI-ROYAL(厚声)")
        (field (name "MANUFACTURER PART") "0402WGF4702TCE")
      )
      (libsource (lib "kernel") (part "0402WGF4702TCE"))
    )
    (comp (ref "R26")
      (value "2K")
      (footprint "0402_R")
      (description "电阻2K")
      (fields
        (field (name "MANUFACTURER") "UNI-ROYAL(厚声)")
        (field (name "MANUFACTURER PART") "0402WGF1002TCE")
      )
      (libsource (lib "kernel") (part "0402WGF2001TCE"))
    )
    (comp (ref "R27")
      (value "100K")
      (footprint "0402_R")
      (description "电阻100K")
      (fields
        (field (name "MANUFACTURER") "UNI-ROYAL(厚声)")
        (field (name "MANUFACTURER PART") "0402WGF1002TCE")
      )
      (libsource (lib "Schlib1") (part "0402WGF1003TCE"))
    )
    (comp (ref "R28")
      (value "100K")
      (footprint "0402_R")
      (description "电阻100K")
      (fields
        (field (name "MANUFACTURER") "UNI-ROYAL(厚声)")
        (field (name "MANUFACTURER PART") "0402WGF1002TCE")
      )
      (libsource (lib "Schlib1") (part "0402WGF1003TCE"))
    )
    (comp (ref "R29")
      (value "2K")
      (footprint "0402_R")
      (description "电阻2K")
      (fields
        (field (name "MANUFACTURER") "UNI-ROYAL(厚声)")
        (field (name "MANUFACTURER PART") "0402WGF1002TCE")
      )
      (libsource (lib "kernel") (part "0402WGF2001TCE"))
    )
    (comp (ref "R30")
      (value "10K")
      (footprint "0402_R")
      (description "电阻10K")
      (fields
        (field (name "MANUFACTURER") "UNI-ROYAL(厚声)")
        (field (name "MANUFACTURER PART") "0402WGF1002TCE")
      )
      (libsource (lib "altium-import") (part "root_1_0402WGF1002TCE_"))
    )
    (comp (ref "R31")
      (value "2K")
      (footprint "0402_R")
      (description "电阻2K")
      (fields
        (field (name "MANUFACTURER") "UNI-ROYAL(厚声)")
        (field (name "MANUFACTURER PART") "0402WGF1002TCE")
      )
      (libsource (lib "kernel") (part "0402WGF2001TCE"))
    )
    (comp (ref "R32")
      (value "510R")
      (footprint "0603_R")
      (description "电阻510R")
      (fields
        (field (name "MANUFACTURER") "UNI-ROYAL(厚声)")
        (field (name "MANUFACTURER PART") "0603WAF5100T5E")
      )
      (libsource (lib "altium-import") (part "root_0_0603WAF5100T5E_"))
    )
    (comp (ref "R33")
      (value "100K")
      (footprint "0402_R")
      (description "电阻100K")
      (fields
        (field (name "MANUFACTURER") "UNI-ROYAL(厚声)")
        (field (name "MANUFACTURER PART") "0402WGF1002TCE")
      )
      (libsource (lib "kernel") (part "0402WGF1003TCE"))
    )
    (comp (ref "R34")
      (value "10K")
      (footprint "0402_R")
      (description "电阻10K")
      (fields
        (field (name "MANUFACTURER") "UNI-ROYAL(厚声)")
        (field (name "MANUFACTURER PART") "0402WGF1002TCE")
      )
      (libsource (lib "altium-import") (part "root_1_0402WGF1002TCE_"))
    )
    (comp (ref "R35")
      (value "1K")
      (footprint "0402_R")
      (description "电阻1K")
      (fields
        (field (name "MANUFACTURER") "UNI-ROYAL(厚声)")
        (field (name "MANUFACTURER PART") "0402WGF1001TCE")
      )
      (libsource (lib "Schlib1") (part "0402WGF1001TCE"))
    )
    (comp (ref "R36")
      (value "10K")
      (footprint "0402_R")
      (description "电阻10K")
      (fields
        (field (name "MANUFACTURER") "UNI-ROYAL(厚声)")
        (field (name "MANUFACTURER PART") "0402WGF1002TCE")
      )
      (libsource (lib "altium-import") (part "root_2_0402WGF1002TCE_"))
    )
    (comp (ref "R37")
      (value "1K")
      (footprint "0402_R")
      (description "电阻1K")
      (fields
        (field (name "MANUFACTURER") "UNI-ROYAL(厚声)")
        (field (name "MANUFACTURER PART") "0402WGF1001TCE")
      )
      (libsource (lib "Schlib1") (part "0402WGF1001TCE"))
    )
    (comp (ref "R38")
      (value "2K")
      (footprint "0402_R")
      (description "电阻2K")
      (fields
        (field (name "MANUFACTURER") "UNI-ROYAL(厚声)")
        (field (name "MANUFACTURER PART") "0402WGF1002TCE")
      )
      (libsource (lib "altium-import") (part "root_0_0402WGF2001TCE_"))
    )
    (comp (ref "R39")
      (value "10K")
      (footprint "0402_R")
      (description "电阻10K")
      (fields
        (field (name "MANUFACTURER") "UNI-ROYAL(厚声)")
        (field (name "MANUFACTURER PART") "0402WGF1002TCE")
      )
      (libsource (lib "altium-import") (part "root_3_0402WGF1002TCE_"))
    )
    (comp (ref "R40")
      (value "1K")
      (footprint "0402_R")
      (description "电阻1K")
      (fields
        (field (name "MANUFACTURER") "UNI-ROYAL(厚声)")
        (field (name "MANUFACTURER PART") "0402WGF1001TCE")
      )
      (libsource (lib "kernel") (part "0402WGF1001TCE"))
    )
    (comp (ref "R41")
      (value "10K")
      (footprint "0402_R")
      (description "电阻10K")
      (fields
        (field (name "MANUFACTURER") "UNI-ROYAL(厚声)")
        (field (name "MANUFACTURER PART") "0402WGF1002TCE")
      )
      (libsource (lib "kernel") (part "0402WGF1002TCE"))
    )
    (comp (ref "R44")
      (value "2K")
      (footprint "0402_R")
      (description "电阻2K")
      (fields
        (field (name "MANUFACTURER") "UNI-ROYAL(厚声)")
        (field (name "MANUFACTURER PART") "0402WGF1002TCE")
      )
      (libsource (lib "altium-import") (part "root_0_0402WGF2001TCE_"))
    )
    (comp (ref "R45")
      (value "10K")
      (footprint "0402_R")
      (description "电阻10K")
      (fields
        (field (name "MANUFACTURER") "UNI-ROYAL(厚声)")
        (field (name "MANUFACTURER PART") "0402WGF1002TCE")
      )
      (libsource (lib "altium-import") (part "root_3_0402WGF1002TCE_"))
    )
    (comp (ref "R46")
      (value "10K")
      (footprint "0402_R")
      (description "电阻10K")
      (fields
        (field (name "MANUFACTURER") "UNI-ROYAL(厚声)")
        (field (name "MANUFACTURER PART") "0402WGF1002TCE")
      )
      (libsource (lib "altium-import") (part "root_3_0402WGF1002TCE_"))
    )
    (comp (ref "R47")
      (value "2K")
      (footprint "0402_R")
      (description "电阻2K")
      (fields
        (field (name "MANUFACTURER") "UNI-ROYAL(厚声)")
        (field (name "MANUFACTURER PART") "0402WGF1002TCE")
      )
      (libsource (lib "altium-import") (part "root_0_0402WGF2001TCE_"))
    )
    (comp (ref "R48")
      (value "10K")
      (footprint "0402_R")
      (description "电阻10K")
      (fields
        (field (name "MANUFACTURER") "UNI-ROYAL(厚声)")
        (field (name "MANUFACTURER PART") "0402WGF1002TCE")
      )
      (libsource (lib "altium-import") (part "root_3_0402WGF1002TCE_"))
    )
    (comp (ref "R49")
      (value "100R")
      (footprint "0402_R")
      (description "电阻100R")
      (fields
        (field (name "MANUFACTURER") "UNI-ROYAL(厚声)")
        (field (name "MANUFACTURER PART") "0402WGF1000TCE")
      )
      (libsource (lib "altium-import") (part "root_0_0402WGF1000TCE_"))
    )
    (comp (ref "R50")
      (value "10K")
      (footprint "0402_R")
      (description "电阻10K")
      (fields
        (field (name "MANUFACTURER") "UNI-ROYAL(厚声)")
        (field (name "MANUFACTURER PART") "0402WGF1002TCE")
      )
      (libsource (lib "altium-import") (part "root_0_0402WGF1002TCE_"))
    )
    (comp (ref "R51")
      (value "10K")
      (footprint "0402_R")
      (description "电阻10K")
      (fields
        (field (name "MANUFACTURER") "UNI-ROYAL(厚声)")
        (field (name "MANUFACTURER PART") "0402WGF1002TCE")
      )
      (libsource (lib "altium-import") (part "root_0_0402WGF1002TCE_"))
    )
    (comp (ref "R52")
      (value "22K")
      (footprint "0402_R")
      (description "电阻47K")
      (fields
        (field (name "MANUFACTURER") "UNI-ROYAL(厚声)")
        (field (name "MANUFACTURER PART") "0402WGF4702TCE")
      )
      (libsource (lib "kernel") (part "0402WGF4702TCE"))
    )
    (comp (ref "R53")
      (value "47K")
      (footprint "0402_R")
      (description "电阻22K")
      (fields
        (field (name "MANUFACTURER") "UNI-ROYAL(厚声)")
        (field (name "MANUFACTURER PART") "0402WGF4702TCE")
      )
      (libsource (lib "kernel") (part "0402WGF2202TCE"))
    )
    (comp (ref "R54")
      (value "10K")
      (footprint "0402_R")
      (description "电阻10K")
      (fields
        (field (name "MANUFACTURER") "UNI-ROYAL(厚声)")
        (field (name "MANUFACTURER PART") "0402WGF1002TCE")
      )
      (libsource (lib "altium-import") (part "root_0_0402WGF1002TCE_"))
    )
    (comp (ref "R55")
      (value "10K")
      (footprint "0402_R")
      (description "电阻10K")
      (fields
        (field (name "MANUFACTURER") "UNI-ROYAL(厚声)")
        (field (name "MANUFACTURER PART") "0402WGF1002TCE")
      )
      (libsource (lib "altium-import") (part "root_0_0402WGF1002TCE_"))
    )
    (comp (ref "U1")
      (value "TP4056")
      (footprint "ESOP-8_L4.9-W3.9-P1.27-LS6.0-BL-EP")
      (description "锂电池充电管理IC")
      (fields (field (name "MANUFACTURER") "UMW(友台半导体)"))
      (libsource (lib "power") (part "TP4056_C725790"))
    )
    (comp (ref "U2")
      (value "LAN8720A-CP-TR")
      (footprint "QFN-24_L4.0-W4.0-P0.50-BL-EP2.6")
      (description "ETHER_PHY")
      (fields (field (name "MANUFACTURER") "MICROCHIP(美国微芯)"))
      (libsource (lib "altium-import") (part "root_0_LAN8720A-CP-TR_"))
    )
    (comp (ref "U3")
      (value "AMS1117-3.3V")
      (footprint "SOT-89-3_L4.5-W2.5-P1.50-LS4.2-BR")
      (fields (field (name "MANUFACTURER") "MSKSEMI(美森科)"))
      (libsource (lib "power") (part "AMS1117-3.3V_C5120796"))
    )
    (comp (ref "U4")
      (value "AMS1117-3.3V")
      (footprint "SOT-89-3_L4.5-W2.5-P1.50-LS4.2-BR")
      (fields (field (name "MANUFACTURER") "MSKSEMI(美森科)"))
      (libsource (lib "power") (part "AMS1117-3.3V_C5120796"))
    )
    (comp (ref "U5") (value "DX-WF24") (footprint "DX-WF24-SMT") (libsource (lib "Schlib1") (part "DX-WF24")))
    (comp (ref "U6")
      (value "W25Q128JVSIQ")
      (footprint "SOIC-8_L5.3-W5.3-P1.27-LS8.0-BL")
      (description "QSPI Norflash")
      (fields (field (name "MANUFACTURER") "Winbond(华邦)"))
      (libsource (lib "Schlib1") (part "W25Q128JVSIQ"))
    )
    (comp (ref "U7")
      (value "W9825G6KH-6")
      (footprint "TSOP-54_L22.2-W10.2-P0.80-LS11.8-BL")
      (description "SDRAM")
      (fields (field (name "MANUFACTURER") "Winbond(华邦)"))
      (libsource (lib "altium-import") (part "root_0_W9825G6KH-6_"))
    )
    (comp (ref "U8")
      (value "STM32F429IGT6")
      (footprint "LQFP-176_L24.0-W24.0-P0.50-LS26.0-BL")
      (description "主控")
      (fields (field (name "MANUFACTURER") "ST(意法半导体)"))
      (libsource (lib "altium-import") (part "root_0_STM32F429IGT6_"))
    )
    (comp (ref "USB1")
      (value "TYPE-C 6P")
      (footprint "TYPE-C-SMD_TYPE-C-6P")
      (fields (field (name "MANUFACTURER") "SHOU HAN(首韩)"))
      (libsource (lib "power") (part "TYPE-C 6P"))
    )
    (comp (ref "X1")
      (value "25M")
      (footprint "SMD-3225_4P")
      (description "25Mhz")
      (fields (field (name "DESIGNER") "U?"))
      (libsource (lib "altium-import") (part "root_0_XL2EL89CSI-111YLC-25M_"))
    )
    (comp (ref "X2")
      (value "25M")
      (footprint "SMD-3225_4P")
      (description "25Mhz")
      (fields (field (name "DESIGNER") "U?"))
      (libsource (lib "altium-import") (part "root_0_XL2EL89CSI-111YLC-25M_"))
    )
    (comp (ref "X3")
      (value "32.768K")
      (footprint "SMD3225-2P")
      (description "RTC时钟晶振")
      (fields (field (name "MANUFACTURER") "同晶") (field (name "MANUFACTURER PART") "XTF32032768JT00351011"))
      (libsource (lib "altium-import") (part "root_0_XTF32032768JT00351011_"))
    )
  )
  (nets
    (net (code "1") (name "/15V") (class "Default")
      (node (ref "J5") (pin "2") (pinfunction "2_2") (pintype "passive"))
      (node (ref "J5") (pin "41") (pinfunction "41_41") (pintype "passive"))
    )
    (net (code "2") (name "/B0") (class "Default")
      (node (ref "J5") (pin "21") (pinfunction "21_21") (pintype "passive"))
      (node (ref "U8") (pin "3") (pinfunction "PE4/SPI4_NSS/SAI1_FS_A/FMC_A20/DCMI_D4/LCD_B0_3") (pintype "passive"))
    )
    (net (code "3") (name "/B1") (class "Default")
      (node (ref "J5") (pin "22") (pinfunction "22_22") (pintype "passive"))
      (node (ref "U8") (pin "155") (pinfunction "PG12/SPI6_MISO/U6_RTS/FMC_NE4/LCD_B1/LCD_B4_155") (pintype "passive"))
    )
    (net (code "4") (name "/B2") (class "Default")
      (node (ref "J5") (pin "23") (pinfunction "23_23") (pintype "passive"))
      (node (ref "U8") (pin "153") (pinfunction "PG10/LCD_G3/FMC_NE3/FMC_NCE4_1/DCMI_D2/LCD_B2_153") (pintype "passive"))
    )
    (net (code "5") (name "/B3") (class "Default")
      (node (ref "J5") (pin "24") (pinfunction "24_24") (pintype "passive"))
      (node (ref "U8") (pin "154") (pinfunction "PG11/ETH_MII_TX_EN/ETH_RMII_TX_EN/FMC_NCE4_2/DCMI_D3/LCD_B3_154") (pintype "passive"))
    )
    (net (code "6") (name "/B4") (class "Default")
      (node (ref "J5") (pin "25") (pinfunction "25_25") (pintype "passive"))
      (node (ref "U8") (pin "173") (pinfunction "PI4/TIM8_BKIN/FMC_NBL2/DCMI_D5/LCD_B4_173") (pintype "passive"))
    )
    (net (code "7") (name "/B5") (class "Default")
      (node (ref "J5") (pin "26") (pinfunction "26_26") (pintype "passive"))
      (node (ref "U8") (pin "174") (pinfunction "PI5/TIM8_CH1/FMC_NBL3/DCMI_VSYNC/LCD_B5_174") (pintype "passive"))
    )
    (net (code "8") (name "/B6") (class "Default")
      (node (ref "J5") (pin "27") (pinfunction "27_27") (pintype "passive"))
      (node (ref "U8") (pin "175") (pinfunction "PI6/TIM8_CH2/FMC_D28/DCMI_D6/LCD_B6_175") (pintype "passive"))
    )
    (net (code "9") (name "/B7") (class "Default")
      (node (ref "J5") (pin "28") (pinfunction "28_28") (pintype "passive"))
      (node (ref "U8") (pin "176") (pinfunction "PI7/TIM8_CH3/FMC_D29/DCMI_D7/LCD_B7_176") (pintype "passive"))
    )
    (net (code "10") (name "/BAT_VOL") (class "Default")
      (node (ref "R52") (pin "1") (pinfunction "1_1") (pintype "passive"))
      (node (ref "R53") (pin "2") (pinfunction "2_2") (pintype "passive"))
      (node (ref "U8") (pin "52") (pinfunction "PA6/TIM1_BKIN/TIM3_CH1/TIM8_BKIN/SPI1_MISO/TIM13_CH1/DCMI_PIXCLK/LCD_G2/ADC12_IN6_52") (pintype "passive"))
    )
    (net (code "11") (name "/BOOT0") (class "Default")
      (node (ref "R50") (pin "1") (pinfunction "1_1") (pintype "passive"))
      (node (ref "U8") (pin "166") (pinfunction "BOOT0_166") (pintype "passive"))
    )
    (net (code "12") (name "/BOOT1") (class "Default")
      (node (ref "R51") (pin "1") (pinfunction "1_1") (pintype "passive"))
      (node (ref "U8") (pin "58") (pinfunction "PB2/BOOT1_58") (pintype "passive"))
    )
    (net (code "13") (name "/CLK") (class "Default")
      (node (ref "J5") (pin "30") (pinfunction "30_30") (pintype "passive"))
      (node (ref "U8") (pin "111") (pinfunction "PG7/U6_CK/FMC_INT3/DCMI_D13/LCD_CLK_111") (pintype "passive"))
    )
    (net (code "14") (name "/CS") (class "Default")
      (node (ref "J5") (pin "40") (pinfunction "40_40") (pintype "passive"))
      (node (ref "U8") (pin "168") (pinfunction "PB9/TIM4_CH4/TIM11_CH1/I2C1_SDA/SPI2_NSS/I2S2_WS/CAN1_TX/SDIO_D5/DCMI_D7/LCD_B7_168") (pintype "passive"))
    )
    (net (code "15") (name "/DEN") (class "Default")
      (node (ref "J5") (pin "34") (pinfunction "34_34") (pintype "passive"))
      (node (ref "U8") (pin "28") (pinfunction "PF10/FMC_INTR/DCMI_D11/LCD_DE/ADC3_IN8_28") (pintype "passive"))
    )
    (net (code "16") (name "/ETH_MDC") (class "Default")
      (node (ref "U2") (pin "13") (pinfunction "MDC_13") (pintype "passive"))
      (node (ref "U8") (pin "33") (pinfunction "PC1/ETH_MDC/ADC123_IN11_33") (pintype "passive"))
    )
    (net (code "17") (name "/ETH_MDIO") (class "Default")
      (node (ref "R6") (pin "1") (pinfunction "1_1") (pintype "passive"))
      (node (ref "U8") (pin "42") (pinfunction "PA2/TIM2_CH3/TIM5_CH3/TIM9_CH1/U2_TX/ETH_MDIO/ADC123_IN2_42") (pintype "passive"))
    )
    (net (code "18") (name "/ETH_RESET") (class "Default")
      (node (ref "U2") (pin "15") (pinfunction "nRST_15") (pintype "passive"))
      (node (ref "U8") (pin "99") (pinfunction "PD11/U3_CTS/FMC_A16_99") (pintype "passive"))
    )
    (net (code "19") (name "/FMC_A0") (class "Default")
      (node (ref "U7") (pin "23") (pinfunction "A0_23") (pintype "passive"))
      (node (ref "U8") (pin "16") (pinfunction "PF0/I2C2_SDA/FMC_A0_16") (pintype "passive"))
    )
    (net (code "20") (name "/FMC_A1") (class "Default")
      (node (ref "U7") (pin "24") (pinfunction "A1_24") (pintype "passive"))
      (node (ref "U8") (pin "17") (pinfunction "PF1/I2C2_SCL/FMC_A1_17") (pintype "passive"))
    )
    (net (code "21") (name "/FMC_A2") (class "Default")
      (node (ref "U7") (pin "25") (pinfunction "A2_25") (pintype "passive"))
      (node (ref "U8") (pin "18") (pinfunction "PF2/I2C2_SMBA/FMC_A2_18") (pintype "passive"))
    )
    (net (code "22") (name "/FMC_A3") (class "Default")
      (node (ref "U7") (pin "26") (pinfunction "A3_26") (pintype "passive"))
      (node (ref "U8") (pin "19") (pinfunction "PF3/FMC_A3/ADC3_IN9_19") (pintype "passive"))
    )
    (net (code "23") (name "/FMC_A4") (class "Default")
      (node (ref "U7") (pin "29") (pinfunction "A4_29") (pintype "passive"))
      (node (ref "U8") (pin "20") (pinfunction "PF4/FMC_A4/ADC3_IN14_20") (pintype "passive"))
    )
    (net (code "24") (name "/FMC_A5") (class "Default")
      (node (ref "U7") (pin "30") (pinfunction "A5_30") (pintype "passive"))
      (node (ref "U8") (pin "21") (pinfunction "PF5/FMC_A5/ADC3_IN15_21") (pintype "passive"))
    )
    (net (code "25") (name "/FMC_A6") (class "Default")
      (node (ref "U7") (pin "31") (pinfunction "A6_31") (pintype "passive"))
      (node (ref "U8") (pin "60") (pinfunction "PF12/FMC_A6_60") (pintype "passive"))
    )
    (net (code "26") (name "/FMC_A7") (class "Default")
      (node (ref "U7") (pin "32") (pinfunction "A7_32") (pintype "passive"))
      (node (ref "U8") (pin "63") (pinfunction "PF13/FMC_A7_63") (pintype "passive"))
    )
    (net (code "27") (name "/FMC_A8") (class "Default")
      (node (ref "U7") (pin "33") (pinfunction "A8_33") (pintype "passive"))
      (node (ref "U8") (pin "64") (pinfunction "PF14/FMC_A8_64") (pintype "passive"))
    )
    (net (code "28") (name "/FMC_A9") (class "Default")
      (node (ref "U7") (pin "34") (pinfunction "A9_34") (pintype "passive"))
      (node (ref "U8") (pin "65") (pinfunction "PF15/FMC_A9_65") (pintype "passive"))
    )
    (net (code "29") (name "/FMC_A10") (class "Default")
      (node (ref "U7") (pin "22") (pinfunction "A10/AP_22") (pintype "passive"))
      (node (ref "U8") (pin "66") (pinfunction "PG0/FMC_A10_66") (pintype "passive"))
    )
    (net (code "30") (name "/FMC_A11") (class "Default")
      (node (ref "U7") (pin "35") (pinfunction "A11_35") (pintype "passive"))
      (node (ref "U8") (pin "67") (pinfunction "PG1/FMC_A11_67") (pintype "passive"))
    )
    (net (code "31") (name "/FMC_A12") (class "Default")
      (node (ref "U7") (pin "36") (pinfunction "A12_36") (pintype "passive"))
      (node (ref "U8") (pin "106") (pinfunction "PG2/FMC_A12_106") (pintype "passive"))
    )
    (net (code "32") (name "/FMC_BA0") (class "Default")
      (node (ref "U7") (pin "20") (pinfunction "BS0_20") (pintype "passive"))
      (node (ref "U8") (pin "108") (pinfunction "PG4/FMC_A14/FMC_BA0_108") (pintype "passive"))
    )
    (net (code "33") (name "/FMC_BA1") (class "Default")
      (node (ref "U7") (pin "21") (pinfunction "BS1_21") (pintype "passive"))
      (node (ref "U8") (pin "109") (pinfunction "PG5/FMC_A15/FMC_BA1_109") (pintype "passive"))
    )
    (net (code "34") (name "/FMC_D0") (class "Default")
      (node (ref "U7") (pin "2") (pinfunction "DQ0_2") (pintype "passive"))
      (node (ref "U8") (pin "104") (pinfunction "PD14/TIM4_CH3/FMC_D0_104") (pintype "passive"))
    )
    (net (code "35") (name "/FMC_D1") (class "Default")
      (node (ref "U7") (pin "4") (pinfunction "DQ1_4") (pintype "passive"))
      (node (ref "U8") (pin "105") (pinfunction "PD15/TIM4_CH4/FMC_D1_105") (pintype "passive"))
    )
    (net (code "36") (name "/FMC_D2") (class "Default")
      (node (ref "U7") (pin "5") (pinfunction "DQ2_5") (pintype "passive"))
      (node (ref "U8") (pin "142") (pinfunction "PD0/CAN1_RX/FMC_D2_142") (pintype "passive"))
    )
    (net (code "37") (name "/FMC_D3") (class "Default")
      (node (ref "U7") (pin "7") (pinfunction "DQ3_7") (pintype "passive"))
      (node (ref "U8") (pin "143") (pinfunction "PD1/CAN1_TX/FMC_D3_143") (pintype "passive"))
    )
    (net (code "38") (name "/FMC_D4") (class "Default")
      (node (ref "U7") (pin "8") (pinfunction "DQ4_8") (pintype "passive"))
      (node (ref "U8") (pin "68") (pinfunction "PE7/TIM1_ETR/U7_RX/FMC_D4_68") (pintype "passive"))
    )
    (net (code "39") (name "/FMC_D5") (class "Default")
      (node (ref "U7") (pin "10") (pinfunction "DQ5_10") (pintype "passive"))
      (node (ref "U8") (pin "69") (pinfunction "PE8/TIM1_CH1N/U7_TX/FMC_D5_69") (pintype "passive"))
    )
    (net (code "40") (name "/FMC_D6") (class "Default")
      (node (ref "U7") (pin "11") (pinfunction "DQ6_11") (pintype "passive"))
      (node (ref "U8") (pin "70") (pinfunction "PE9/TIM1_CH1/FMC_D6_70") (pintype "passive"))
    )
    (net (code "41") (name "/FMC_D7") (class "Default")
      (node (ref "U7") (pin "13") (pinfunction "DQ7_13") (pintype "passive"))
      (node (ref "U8") (pin "73") (pinfunction "PE10/TIM1_CH2N/FMC_D7_73") (pintype "passive"))
    )
    (net (code "42") (name "/FMC_D8") (class "Default")
      (node (ref "U7") (pin "42") (pinfunction "DQ8_42") (pintype "passive"))
      (node (ref "U8") (pin "74") (pinfunction "PE11/TIM1_CH2/SPI4_NSS/FMC_D8/LCD_G3_74") (pintype "passive"))
    )
    (net (code "43") (name "/FMC_D9") (class "Default")
      (node (ref "U7") (pin "44") (pinfunction "DQ9_44") (pintype "passive"))
      (node (ref "U8") (pin "75") (pinfunction "PE12/TIM1_CH3N/SPI4_SCK/FMC_D9/LCD_B4_75") (pintype "passive"))
    )
    (net (code "44") (name "/FMC_D10") (class "Default")
      (node (ref "U7") (pin "45") (pinfunction "DQ10_45") (pintype "passive"))
      (node (ref "U8") (pin "76") (pinfunction "PE13/TIM1_CH3/SPI4_MISO/FMC_D10/LCD_DE_76") (pintype "passive"))
    )
    (net (code "45") (name "/FMC_D11") (class "Default")
      (node (ref "U7") (pin "47") (pinfunction "DQ11_47") (pintype "passive"))
      (node (ref "U8") (pin "77") (pinfunction "PE14/TIM1_CH4/SPI4_MOSI/FMC_D11/LCD_CLK_77") (pintype "passive"))
    )
    (net (code "46") (name "/FMC_D12") (class "Default")
      (node (ref "U7") (pin "48") (pinfunction "DQ12_48") (pintype "passive"))
      (node (ref "U8") (pin "78") (pinfunction "PE15/TIM1_BKIN/FMC_D12/LCD_R7_78") (pintype "passive"))
    )
    (net (code "47") (name "/FMC_D13") (class "Default")
      (node (ref "U7") (pin "50") (pinfunction "DQ13_50") (pintype "passive"))
      (node (ref "U8") (pin "96") (pinfunction "PD8/U3_TX/FMC_D13_96") (pintype "passive"))
    )
    (net (code "48") (name "/FMC_D14") (class "Default")
      (node (ref "U7") (pin "51") (pinfunction "DQ14_51") (pintype "passive"))
      (node (ref "U8") (pin "97") (pinfunction "PD9/U3_RX/FMC_D14_97") (pintype "passive"))
    )
    (net (code "49") (name "/FMC_D15") (class "Default")
      (node (ref "U7") (pin "53") (pinfunction "DQ15_53") (pintype "passive"))
      (node (ref "U8") (pin "98") (pinfunction "PD10/U3_CK/FMC_D15/LCD_B3_98") (pintype "passive"))
    )
    (net (code "50") (name "/FMC_NBL0") (class "Default")
      (node (ref "U7") (pin "15") (pinfunction "LDQM_15") (pintype "passive"))
      (node (ref "U8") (pin "169") (pinfunction "PE0/TIM4_ETR/U8_RX/FMC_NBL0/DCMI_D2_169") (pintype "passive"))
    )
    (net (code "51") (name "/FMC_NBL1") (class "Default")
      (node (ref "U7") (pin "39") (pinfunction "UDQM_39") (pintype "passive"))
      (node (ref "U8") (pin "170") (pinfunction "PE1/U8_TX/FMC_NBL1/DCMI_D3_170") (pintype "passive"))
    )
    (net (code "52") (name "/FMC_SDCKE0") (class "Default")
      (node (ref "U7") (pin "37") (pinfunction "CKE_37") (pintype "passive"))
      (node (ref "U8") (pin "35") (pinfunction "PC3/SPI2_MOSI/I2S2_SD/OTG_HS_ULPI_NXT/ETH_MII_TX_CLK/FMC_SDCKE0/ADC123_IN13_35") (pintype "passive"))
    )
    (net (code "53") (name "/FMC_SDCLK") (class "Default")
      (node (ref "U7") (pin "38") (pinfunction "CLK_38") (pintype "passive"))
      (node (ref "U8") (pin "112") (pinfunction "PG8/SPI6_NSS/U6_RTS/ETH_PPS_OUT/FMC_SDCLK_112") (pintype "passive"))
    )
    (net (code "54") (name "/FMC_SDNCAS") (class "Default")
      (node (ref "U7") (pin "17") (pinfunction "CAS#_17") (pintype "passive"))
      (node (ref "U8") (pin "160") (pinfunction "PG15/U6_CTS/FMC_SDNCAS/DCMI_D13_160") (pintype "passive"))
    )
    (net (code "55") (name "/FMC_SDNE0") (class "Default")
      (node (ref "U7") (pin "19") (pinfunction "CS#_19") (pintype "passive"))
      (node (ref "U8") (pin "34") (pinfunction "PC2/SPI2_MISO/I2S2ext_SD/OTG_HS_ULPI_DIR/ETH_MII_TXD2/FMC_SDNE0/ADC123_IN12_34") (pintype "passive"))
    )
    (net (code "56") (name "/FMC_SDNRAS") (class "Default")
      (node (ref "U7") (pin "18") (pinfunction "RAS#_18") (pintype "passive"))
      (node (ref "U8") (pin "59") (pinfunction "PF11/SPI5_MOSI/FMC_SDNRAS/DCMI_D12_59") (pintype "passive"))
    )
    (net (code "57") (name "/FMC_SDNWE") (class "Default")
      (node (ref "U7") (pin "16") (pinfunction "WE#_16") (pintype "passive"))
      (node (ref "U8") (pin "32") (pinfunction "PC0/OTG_HS_ULPI_STP/FMC_SDNWE/ADC123_IN10_32") (pintype "passive"))
    )
    (net (code "58") (name "/G0") (class "Default")
      (node (ref "J5") (pin "13") (pinfunction "13_13") (pintype "passive"))
      (node (ref "U8") (pin "4") (pinfunction "PE5/TIM9_CH1/SPI4_MISO/SAI1_SCK_A/FMC_A21/DCMI_D6/LCD_G0_4") (pintype "passive"))
    )
    (net (code "59") (name "/G1") (class "Default")
      (node (ref "J5") (pin "14") (pinfunction "14_14") (pintype "passive"))
      (node (ref "U8") (pin "5") (pinfunction "PE6/TIM9_CH2/SPI4_MOSI/SAI1_SD_A/FMC_A22/DCMI_D7/LCD_G1_5") (pintype "passive"))
    )
    (net (code "60") (name "/G2") (class "Default")
      (node (ref "J5") (pin "15") (pinfunction "15_15") (pintype "passive"))
      (node (ref "U8") (pin "128") (pinfunction "PH13/TIM8_CH1N/CAN1_TX/FMC_D21/LCD_G2_128") (pintype "passive"))
    )
    (net (code "61") (name "/G3") (class "Default")
      (node (ref "J5") (pin "16") (pinfunction "16_16") (pintype "passive"))
      (node (ref "U8") (pin "129") (pinfunction "PH14/TIM8_CH2N/FMC_D22/DCMI_D4/LCD_G3_129") (pintype "passive"))
    )
    (net (code "62") (name "/G4") (class "Default")
      (node (ref "J5") (pin "17") (pinfunction "17_17") (pintype "passive"))
      (node (ref "U8") (pin "130") (pinfunction "PH15/TIM8_CH3N/FMC_D23/DCMI_D11/LCD_G4_130") (pintype "passive"))
    )
    (net (code "63") (name "/G5") (class "Default")
      (node (ref "J5") (pin "18") (pinfunction "18_18") (pintype "passive"))
      (node (ref "U8") (pin "131") (pinfunction "PI0/TIM5_CH4/SPI2_NSS/I2S2_WS/FMC_D24/DCMI_D13/LCD_G5_131") (pintype "passive"))
    )
    (net (code "64") (name "/G6") (class "Default")
      (node (ref "J5") (pin "19") (pinfunction "19_19") (pintype "passive"))
      (node (ref "U8") (pin "132") (pinfunction "PI1/SPI2_SCK/I2S2_CK/FMC_D25/DCMI_D8/LCD_G6_132") (pintype "passive"))
    )
    (net (code "65") (name "/G7") (class "Default")
      (node (ref "J5") (pin "20") (pinfunction "20_20") (pintype "passive"))
      (node (ref "U8") (pin "133") (pinfunction "PI2/TIM8_CH4/SPI2_MISO/I2S2ext_SD/FMC_D26/DCMI_D9/LCD_G7_133") (pintype "passive"))
    )
    (net (code "66") (name "/HSYNC") (class "Default")
      (node (ref "J5") (pin "32") (pinfunction "32_32") (pintype "passive"))
      (node (ref "U8") (pin "12") (pinfunction "PI10/ETH_MII_RX_ER/FMC_D31/LCD_HSYNC_12") (pintype "passive"))
    )
    (net (code "67") (name "/KEY0") (class "Default")
      (node (ref "C22") (pin "2") (pinfunction "2_2") (pintype "passive"))
      (node (ref "R38") (pin "2") (pinfunction "2_2") (pintype "passive"))
      (node (ref "R39") (pin "1") (pinfunction "1_1") (pintype "passive"))
      (node (ref "U8") (pin "140") (pinfunction "PC11/I2S3ext_SD/SPI3_MISO/U3_RX/U4_RX/SDIO_D3/DCMI_D4_140") (pintype "passive"))
    )
    (net (code "68") (name "/KEY1") (class "Default")
      (node (ref "C23") (pin "2") (pinfunction "2_2") (pintype "passive"))
      (node (ref "R44") (pin "2") (pinfunction "2_2") (pintype "passive"))
      (node (ref "R46") (pin "1") (pinfunction "1_1") (pintype "passive"))
      (node (ref "U8") (pin "139") (pinfunction "PC10/SPI3_SCK/I2S3_CK/U3_TX/U4_TX/SDIO_D2/DCMI_D8/LCD_R2_139") (pintype "passive"))
    )
    (net (code "69") (name "/KEY2") (class "Default")
      (node (ref "C24") (pin "2") (pinfunction "2_2") (pintype "passive"))
      (node (ref "R47") (pin "2") (pinfunction "2_2") (pintype "passive"))
      (node (ref "R48") (pin "1") (pinfunction "1_1") (pintype "passive"))
      (node (ref "U8") (pin "8") (pinfunction "PC13/TAMP_1_8") (pintype "passive"))
    )
    (net (code "70") (name "/LCD_RST") (class "Default")
      (node (ref "J5") (pin "37") (pinfunction "37_37") (pintype "passive"))
      (node (ref "U8") (pin "164") (pinfunction "PB6/TIM4_CH1/I2C1_SCL/U1_TX/CAN2_TX/FMC_SDNE1/DCMI_D5_164") (pintype "passive"))
    )
    (net (code "71") (name "/LED") (class "Default")
      (node (ref "D10") (pin "1") (pinfunction "K_1") (pintype "passive"))
      (node (ref "U8") (pin "47") (pinfunction "PA3/TIM2_CH4/TIM5_CH4/TIM9_CH2/U2_RX/OTG_HS_ULPI_D0/ETH_MII_COL/LCD_B5/ADC123_IN3_47") (pintype "passive"))
    )
    (net (code "72") (name "/LEDK") (class "Default")
      (node (ref "R40") (pin "2") (pinfunction "2_2") (pintype "passive"))
      (node (ref "U8") (pin "57") (pinfunction "PB1/TIM1_CH3N/TIM3_CH4/TIM8_CH3N/LCD_R6/OTG_HS_ULPI_D2/ETH_MII_RXD3/ADC12_IN9_57") (pintype "passive"))
    )
    (net (code "73") (name "/LINK") (class "Default")
      (node (ref "J2") (pin "1") (pinfunction "1_1") (pintype "passive"))
      (node (ref "U2") (pin "3") (pinfunction "LED1/REGOFF_3") (pintype "passive"))
    )
    (net (code "74") (name "/MISO") (class "Default")
      (node (ref "U6") (pin "2") (pinfunction "DO_2") (pintype "passive"))
      (node (ref "U8") (pin "26") (pinfunction "PF8/TIM13_CH1/SPI5_MISO/SAI1_SCK_B/FMC_NIOWR/ADC3_IN6_26") (pintype "passive"))
    )
    (net (code "75") (name "/MOSI") (class "Default")
      (node (ref "U6") (pin "5") (pinfunction "DI_5") (pintype "passive"))
      (node (ref "U8") (pin "27") (pinfunction "PF9/TIM14_CH1/SPI5_MOSI/SAI1_FS_B/FMC_CD/ADC3_IN7_27") (pintype "passive"))
    )
    (net (code "76") (name "/OSC1") (class "Default")
      (node (ref "C25") (pin "1") (pinfunction "1_1") (pintype "passive"))
      (node (ref "U8") (pin "29") (pinfunction "PH0/OSC_IN_29") (pintype "passive"))
      (node (ref "X2") (pin "1") (pinfunction "OSC1_1") (pintype "passive"))
    )
    (net (code "77") (name "/OSC2") (class "Default")
      (node (ref "C26") (pin "1") (pinfunction "1_1") (pintype "passive"))
      (node (ref "U8") (pin "30") (pinfunction "PH1/OSC_OUT_30") (pintype "passive"))
      (node (ref "X2") (pin "3") (pinfunction "OSC2_3") (pintype "passive"))
    )
    (net (code "78") (name "/OSC32_IN") (class "Default")
      (node (ref "C27") (pin "2") (pinfunction "2_2") (pintype "passive"))
      (node (ref "U8") (pin "9") (pinfunction "PC14/OSC32_IN_9") (pintype "passive"))
      (node (ref "X3") (pin "1") (pinfunction "1_1") (pintype "passive"))
    )
    (net (code "79") (name "/OSC32_OUT") (class "Default")
      (node (ref "C28") (pin "2") (pinfunction "2_2") (pintype "passive"))
      (node (ref "U8") (pin "10") (pinfunction "PC15/OSC32_OUT_10") (pintype "passive"))
      (node (ref "X3") (pin "2") (pinfunction "2_2") (pintype "passive"))
    )
    (net (code "80") (name "/POWER_DOWN") (class "Default")
      (node (ref "D7") (pin "2") (pinfunction "A_2") (pintype "passive"))
      (node (ref "R23") (pin "1") (pinfunction "1_1") (pintype "passive"))
      (node (ref "U8") (pin "115") (pinfunction "PC6/TIM3_CH1/TIM8_CH1/I2S2_MCK/U6_TX/SDIO_D6/DCMI_D0/LCD_HSYNC_115") (pintype "passive"))
    )
    (net (code "81") (name "/POWER_M") (class "Default")
      (node (ref "R31") (pin "1") (pinfunction "1_1") (pintype "passive"))
      (node (ref "R33") (pin "2") (pinfunction "2_2") (pintype "passive"))
      (node (ref "U8") (pin "51") (pinfunction "PA5/TIM2_CH1/TIM2_ETR/TIM8_CH1N/SPI1_SCK/OTG_HS_ULPI_CK/ADC12_IN5/DAC_OUT2_51") (pintype "passive"))
    )
    (net (code "82") (name "/POWER_MM") (class "Default")
      (node (ref "R26") (pin "1") (pinfunction "1_1") (pintype "passive"))
      (node (ref "U8") (pin "116") (pinfunction "PC7/TIM3_CH2/TIM8_CH2/I2S3_MCK/U6_RX/SDIO_D7/DCMI_D1/LCD_G6_116") (pintype "passive"))
    )
    (net (code "83") (name "/POWER_P") (class "Default")
      (node (ref "R11") (pin "1") (pinfunction "1_1") (pintype "passive"))
      (node (ref "R16") (pin "1") (pinfunction "1_1") (pintype "passive"))
      (node (ref "U8") (pin "50") (pinfunction "PA4/SPI1_NSS/SPI3_NSS/I2S3_WS/U2_CK/OTG_HS_SOF/DCMI_HSYNC/LCD_VSYNC/ADC12_IN4/DAC_OUT1_50") (pintype "passive"))
    )
    (net (code "84") (name "/R0") (class "Default")
      (node (ref "J5") (pin "5") (pinfunction "5_5") (pintype "passive"))
      (node (ref "U8") (pin "43") (pinfunction "PH2/ETH_MII_CRS/FMC_SDCKE0/LCD_R0_43") (pintype "passive"))
    )
    (net (code "85") (name "/R1") (class "Default")
      (node (ref "J5") (pin "6") (pinfunction "6_6") (pintype "passive"))
      (node (ref "U8") (pin "44") (pinfunction "PH3/ETH_MII_COL/FMC_SDNE0/LCD_R1_44") (pintype "passive"))
    )
    (net (code "86") (name "/R2") (class "Default")
      (node (ref "J5") (pin "7") (pinfunction "7_7") (pintype "passive"))
      (node (ref "U8") (pin "85") (pinfunction "PH8/I2C3_SDA/FMC_D16/DCMI_HSYNC/LCD_R2_85") (pintype "passive"))
    )
    (net (code "87") (name "/R3") (class "Default")
      (node (ref "J5") (pin "8") (pinfunction "8_8") (pintype "passive"))
      (node (ref "U8") (pin "86") (pinfunction "PH9/I2C3_SMBA/TIM12_CH2/FMC_D17/DCMI_D0/LCD_R3_86") (pintype "passive"))
    )
    (net (code "88") (name "/R4") (class "Default")
      (node (ref "J5") (pin "9") (pinfunction "9_9") (pintype "passive"))
      (node (ref "U8") (pin "87") (pinfunction "PH10/TIM5_CH1/FMC_D18/DCMI_D1/LCD_R4_87") (pintype "passive"))
    )
    (net (code "89") (name "/R5") (class "Default")
      (node (ref "J5") (pin "10") (pinfunction "10_10") (pintype "passive"))
      (node (ref "U8") (pin "88") (pinfunction "PH11/TIM5_CH2/FMC_D19/DCMI_D2/LCD_R5_88") (pintype "passive"))
    )
    (net (code "90") (name "/R6") (class "Default")
      (node (ref "J5") (pin "11") (pinfunction "11_11") (pintype "passive"))
      (node (ref "U8") (pin "89") (pinfunction "PH12/TIM5_CH3/FMC_D20/DCMI_D3/LCD_R6_89") (pintype "passive"))
    )
    (net (code "91") (name "/R7") (class "Default")
      (node (ref "J5") (pin "12") (pinfunction "12_12") (pintype "passive"))
      (node (ref "U8") (pin "110") (pinfunction "PG6/FMC_INT2/DCMI_D12/LCD_R7_110") (pintype "passive"))
    )
    (net (code "92") (name "/RMII_CRS_DV") (class "Default")
      (node (ref "U2") (pin "11") (pinfunction "CRS_DV/MODE2_11") (pintype "passive"))
      (node (ref "U8") (pin "53") (pinfunction "PA7/TIM1_CH1N/TIM3_CH2/TIM8_CH1N/SPI1_MOSI/TIM14_CH1/ETH_MII_RX_DV/ETH_RMII_CRS_DV/ADC12_IN7_53") (pintype "passive"))
    )
    (net (code "93") (name "/RMII_REF_CLK") (class "Default")
      (node (ref "U2") (pin "14") (pinfunction "nINT/REFCLKO_14") (pintype "passive"))
      (node (ref "U8") (pin "41") (pinfunction "PA1/TIM2_CH2/TIM5_CH2/U2_RTS/U4_RX/ETH_MII_RX_CLK/ETH_RMII_REF_CLK/ADC123_IN1_41") (pintype "passive"))
    )
    (net (code "94") (name "/RMII_RXD0") (class "Default")
      (node (ref "U2") (pin "8") (pinfunction "RXD0/MODE0_8") (pintype "passive"))
      (node (ref "U8") (pin "54") (pinfunction "PC4/ETH_MII_RXD0/ETH_RMII_RXD0/ADC12_IN14_54") (pintype "passive"))
    )
    (net (code "95") (name "/RMII_RXD1") (class "Default")
      (node (ref "U2") (pin "7") (pinfunction "RXD1/MODE1_7") (pintype "passive"))
      (node (ref "U8") (pin "55") (pinfunction "PC5/ETH_MII_RXD1/ETH_RMII_RXD1/ADC12_IN15_55") (pintype "passive"))
    )
    (net (code "96") (name "/RMII_TXD0") (class "Default")
      (node (ref "U2") (pin "17") (pinfunction "TXD0_17") (pintype "passive"))
      (node (ref "U8") (pin "156") (pinfunction "PG13/SPI6_SCK/U6_CTS/ETH_MII_TXD0/ETH_RMII_TXD0/FMC_A24_156") (pintype "passive"))
    )
    (net (code "97") (name "/RMII_TXD1") (class "Default")
      (node (ref "U2") (pin "18") (pinfunction "TXD1_18") (pintype "passive"))
      (node (ref "U8") (pin "157") (pinfunction "PG14/SPI6_MOSI/U6_TX/ETH_MII_TXD1/ETH_RMII_TXD1/FMC_A25_157") (pintype "passive"))
    )
    (net (code "98") (name "/RMII_TX_EN") (class "Default")
      (node (ref "U2") (pin "16") (pinfunction "TXEN_16") (pintype "passive"))
      (node (ref "U8") (pin "80") (pinfunction "PB11/TIM2_CH4/I2C2_SDA/U3_RX/OTG_HS_ULPI_D4/ETH_MII_TX_EN/ETH_RMII_TX_EN/LCD_G5_80") (pintype "passive"))
    )
    (net (code "99") (name "/SCK") (class "Default")
      (node (ref "U6") (pin "6") (pinfunction "CLK_6") (pintype "passive"))
      (node (ref "U8") (pin "25") (pinfunction "PF7/TIM11_CH1/SPI5_SCK/SAI1_MCLK_B/U7_TX/FMC_NREG/ADC3_IN5_25") (pintype "passive"))
    )
    (net (code "100") (name "/SCL") (class "Default")
      (node (ref "J5") (pin "39") (pinfunction "39_39") (pintype "passive"))
      (node (ref "U8") (pin "167") (pinfunction "PB8/TIM4_CH3/TIM10_CH1/I2C1_SCL/CAN1_RX/ETH_MII_TXD3/SDIO_D4/DCMI_D6/LCD_B6_167") (pintype "passive"))
    )
    (net (code "101") (name "/SDA") (class "Default")
      (node (ref "J5") (pin "38") (pinfunction "38_38") (pintype "passive"))
      (node (ref "U8") (pin "165") (pinfunction "PB7/TIM4_CH2/I2C1_SDA/U1_RX/FMC_NL/DCMI_VSYNC_165") (pintype "passive"))
    )
    (net (code "102") (name "/SPEED") (class "Default")
      (node (ref "J2") (pin "14") (pinfunction "14_14") (pintype "passive"))
      (node (ref "R19") (pin "1") (pinfunction "1_1") (pintype "passive"))
      (node (ref "U2") (pin "2") (pinfunction "LED2/nINTSEL_2") (pintype "passive"))
    )
    (net (code "103") (name "/SPI_CS") (class "Default")
      (node (ref "R30") (pin "1") (pinfunction "1_1") (pintype "passive"))
      (node (ref "U6") (pin "1") (pinfunction "CS#_1") (pintype "passive"))
      (node (ref "U8") (pin "24") (pinfunction "PF6/TIM10_CH1/SPI5_NSS/SAI1_SD_B/U7_RX/FMC_NIORD/ADC3_IN4_24") (pintype "passive"))
    )
    (net (code "104") (name "/SWDCLK") (class "Default")
      (node (ref "J6") (pin "2") (pinfunction "2_2") (pintype "passive"))
      (node (ref "U8") (pin "137") (pinfunction "PA14/JTCK/SWDCLK_137") (pintype "passive"))
    )
    (net (code "105") (name "/SWDIO") (class "Default")
      (node (ref "J6") (pin "3") (pinfunction "3_3") (pintype "passive"))
      (node (ref "R45") (pin "2") (pinfunction "2_2") (pintype "passive"))
      (node (ref "U8") (pin "124") (pinfunction "PA13/JTMS/SWDIO_124") (pintype "passive"))
    )
    (net (code "106") (name "/TPRX_N") (class "Default")
      (node (ref "J2") (pin "4") (pinfunction "4_4") (pintype "passive"))
      (node (ref "R17") (pin "1") (pinfunction "1_1") (pintype "passive"))
      (node (ref "U2") (pin "22") (pinfunction "RXN_22") (pintype "passive"))
    )
    (net (code "107") (name "/TPRX_P") (class "Default")
      (node (ref "J2") (pin "8") (pinfunction "8_8") (pintype "passive"))
      (node (ref "R14") (pin "1") (pinfunction "1_1") (pintype "passive"))
      (node (ref "U2") (pin "23") (pinfunction "RXP_23") (pintype "passive"))
    )
    (net (code "108") (name "/TPTX_N") (class "Default")
      (node (ref "J2") (pin "9") (pinfunction "9_9") (pintype "passive"))
      (node (ref "R9") (pin "1") (pinfunction "1_1") (pintype "passive"))
      (node (ref "U2") (pin "20") (pinfunction "TXN_20") (pintype "passive"))
    )
    (net (code "109") (name "/TPTX_P") (class "Default")
      (node (ref "J2") (pin "10") (pinfunction "10_10") (pintype "passive"))
      (node (ref "R7") (pin "1") (pinfunction "1_1") (pintype "passive"))
      (node (ref "U2") (pin "21") (pinfunction "TXP_21") (pintype "passive"))
    )
    (net (code "110") (name "/VBAT") (class "Default")
      (node (ref "C6") (pin "2") (pinfunction "2_2") (pintype "passive"))
      (node (ref "J1") (pin "1") (pinfunction "V+_1") (pintype "passive"))
      (node (ref "Q1") (pin "3") (pinfunction "D_3") (pintype "passive"))
      (node (ref "R52") (pin "2") (pinfunction "2_2") (pintype "passive"))
      (node (ref "U1") (pin "5") (pinfunction "BAT_5") (pintype "passive"))
    )
    (net (code "111") (name "/VSYNC") (class "Default")
      (node (ref "J5") (pin "33") (pinfunction "33_33") (pintype "passive"))
      (node (ref "U8") (pin "11") (pinfunction "PI9/CAN1_RX/FMC_D30/LCD_VSYNC_11") (pintype "passive"))
    )
    (net (code "112") (name "/WIFI_R") (class "Default")
      (node (ref "R27") (pin "1") (pinfunction "1_1") (pintype "passive"))
      (node (ref "U5") (pin "2") (pinfunction "UART-RX_2") (pintype "passive"))
      (node (ref "U8") (pin "120") (pinfunction "PA9/TIM1_CH2/I2C3_SMBA/U1_TX/DCMI_D0/OTG_FS_VBUS_120") (pintype "passive"))
    )
    (net (code "113") (name "/WIFI_RST") (class "Default")
      (node (ref "R36") (pin "1") (pinfunction "1_1") (pintype "passive"))
      (node (ref "U5") (pin "8") (pinfunction "RST_8") (pintype "passive"))
      (node (ref "U8") (pin "92") (pinfunction "PB12/TIM1_BKIN/I2C2_SMBA/SPI2_NSS/I2S2_WS/U3_CK/CAN2_RX/OTG_HS_ULPI_D5/ETH_MII_TXD0/ETH_RMII_TXD0/OTG_HS_ID_92") (pintype "passive"))
    )
    (net (code "114") (name "/WIFI_T") (class "Default")
      (node (ref "R28") (pin "1") (pinfunction "1_1") (pintype "passive"))
      (node (ref "U5") (pin "1") (pinfunction "UART-TX_1") (pintype "passive"))
      (node (ref "U8") (pin "121") (pinfunction "PA10/TIM1_CH3/U1_RX/OTG_FS_ID/DCMI_D1_121") (pintype "passive"))
    )
    (net (code "115") (name "GND") (class "Default")
      (node (ref "B1") (pin "1") (pinfunction "1_1") (pintype "passive"))
      (node (ref "C1") (pin "1") (pinfunction "1_1") (pintype "passive"))
      (node (ref "C10") (pin "2") (pinfunction "2_2") (pintype "passive"))
      (node (ref "C11") (pin "2") (pinfunction "2_2") (pintype "passive"))
      (node (ref "C12") (pin "1") (pinfunction "1_1") (pintype "passive"))
      (node (ref "C13") (pin "1") (pinfunction "1_1") (pintype "passive"))
      (node (ref "C14") (pin "1") (pinfunction "1_1") (pintype "passive"))
      (node (ref "C15") (pin "1") (pinfunction "1_1") (pintype "passive"))
      (node (ref "C16") (pin "1") (pinfunction "1_1") (pintype "passive"))
      (node (ref "C17") (pin "2") (pinfunction "2_2") (pintype "passive"))
      (node (ref "C18") (pin "2") (pinfunction "2_2") (pintype "passive"))
      (node (ref "C19") (pin "2") (pinfunction "2_2") (pintype "passive"))
      (node (ref "C2") (pin "1") (pinfunction "1_1") (pintype "passive"))
      (node (ref "C20") (pin "1") (pinfunction "1_1") (pintype "passive"))
      (node (ref "C21") (pin "1") (pinfunction "1_1") (pintype "passive"))
      (node (ref "C22") (pin "1") (pinfunction "1_1") (pintype "passive"))
      (node (ref "C23") (pin "1") (pinfunction "1_1") (pintype "passive"))
      (node (ref "C24") (pin "1") (pinfunction "1_1") (pintype "passive"))
      (node (ref "C25") (pin "2") (pinfunction "2_2") (pintype "passive"))
      (node (ref "C26") (pin "2") (pinfunction "2_2") (pintype "passive"))
      (node (ref "C27") (pin "1") (pinfunction "1_1") (pintype "passive"))
      (node (ref "C28") (pin "1") (pinfunction "1_1") (pintype "passive"))
      (node (ref "C29") (pin "2") (pinfunction "2_2") (pintype "passive"))
      (node (ref "C30") (pin "1") (pinfunction "1_1") (pintype "passive"))
      (node (ref "C31") (pin "1") (pinfunction "1_1") (pintype "passive"))
      (node (ref "C32") (pin "1") (pinfunction "1_1") (pintype "passive"))
      (node (ref "C33") (pin "1") (pinfunction "1_1") (pintype "passive"))
      (node (ref "C34") (pin "1") (pinfunction "1_1") (pintype "passive"))
      (node (ref "C35") (pin "1") (pinfunction "1_1") (pintype "passive"))
      (node (ref "C36") (pin "1") (pinfunction "1_1") (pintype "passive"))
      (node (ref "C37") (pin "1") (pinfunction "1_1") (pintype "passive"))
      (node (ref "C38") (pin "1") (pinfunction "1_1") (pintype "passive"))
      (node (ref "C39") (pin "1") (pinfunction "1_1") (pintype "passive"))
      (node (ref "C4") (pin "2") (pinfunction "2_2") (pintype "passive"))
      (node (ref "C40") (pin "1") (pinfunction "1_1") (pintype "passive"))
      (node (ref "C41") (pin "1") (pinfunction "1_1") (pintype "passive"))
      (node (ref "C42") (pin "1") (pinfunction "1_1") (pintype "passive"))
      (node (ref "C43") (pin "1") (pinfunction "1_1") (pintype "passive"))
      (node (ref "C44") (pin "1") (pinfunction "1_1") (pintype "passive"))
      (node (ref "C45") (pin "2") (pinfunction "2_2") (pintype "passive"))
      (node (ref "C46") (pin "1") (pinfunction "1_1") (pintype "passive"))
      (node (ref "C47") (pin "1") (pinfunction "1_1") (pintype "passive"))
      (node (ref "C48") (pin "1") (pinfunction "1_1") (pintype "passive"))
      (node (ref "C49") (pin "1") (pinfunction "1_1") (pintype "passive"))
      (node (ref "C5") (pin "2") (pinfunction "2_2") (pintype "passive"))
      (node (ref "C50") (pin "1") (pinfunction "1_1") (pintype "passive"))
      (node (ref "C51") (pin "1") (pinfunction "1_1") (pintype "passive"))
      (node (ref "C52") (pin "1") (pinfunction "1_1") (pintype "passive"))
      (node (ref "C53") (pin "1") (pinfunction "1_1") (pintype "passive"))
      (node (ref "C54") (pin "2") (pinfunction "2_2") (pintype "passive"))
      (node (ref "C6") (pin "1") (pinfunction "1_1") (pintype "passive"))
      (node (ref "C7") (pin "2") (pinfunction "2_2") (pintype "passive"))
      (node (ref "C8") (pin "1") (pinfunction "1_1") (pintype "passive"))
      (node (ref "C9") (pin "2") (pinfunction "2_2") (pintype "passive"))
      (node (ref "D1") (pin "1") (pinfunction "K_1") (pintype "passive"))
      (node (ref "D2") (pin "1") (pinfunction "K_1") (pintype "passive"))
      (node (ref "J1") (pin "2") (pinfunction "V-_2") (pintype "passive"))
      (node (ref "J2") (pin "11") (pinfunction "11_11") (pintype "passive"))
      (node (ref "J2") (pin "12") (pinfunction "12_12") (pintype "passive"))
      (node (ref "J2") (pin "15") (pinfunction "15_15") (pintype "passive"))
      (node (ref "J2") (pin "16") (pinfunction "16_16") (pintype "passive"))
      (node (ref "J2") (pin "3") (pinfunction "3_3") (pintype "passive"))
      (node (ref "J3") (pin "2") (pinfunction "2_2") (pintype "passive"))
      (node (ref "J5") (pin "29") (pinfunction "29_29") (pintype "passive"))
      (node (ref "J5") (pin "3") (pinfunction "3_3") (pintype "passive"))
      (node (ref "J5") (pin "35") (pinfunction "35_35") (pintype "passive"))
      (node (ref "J5") (pin "36") (pinfunction "36_36") (pintype "passive"))
      (node (ref "J5") (pin "42") (pinfunction "42_42") (pintype "passive"))
      (node (ref "J6") (pin "4") (pinfunction "4_4") (pintype "passive"))
      (node (ref "J6") (pin "6") (pinfunction "6_6") (pintype "passive"))
      (node (ref "J6") (pin "7") (pinfunction "7_7") (pintype "passive"))
      (node (ref "Q3") (pin "2") (pinfunction "E_2") (pintype "passive"))
      (node (ref "Q4") (pin "2") (pinfunction "E_2") (pintype "passive"))
      (node (ref "Q8") (pin "2") (pinfunction "E_2") (pintype "passive"))
      (node (ref "Q9") (pin "2") (pinfunction "E_2") (pintype "passive"))
      (node (ref "R1") (pin "2") (pinfunction "2_2") (pintype "passive"))
      (node (ref "R10") (pin "1") (pinfunction "1_1") (pintype "passive"))
      (node (ref "R11") (pin "2") (pinfunction "2_2") (pintype "passive"))
      (node (ref "R12") (pin "2") (pinfunction "2_2") (pintype "passive"))
      (node (ref "R13") (pin "1") (pinfunction "1_1") (pintype "passive"))
      (node (ref "R19") (pin "2") (pinfunction "2_2") (pintype "passive"))
      (node (ref "R20") (pin "1") (pinfunction "1_1") (pintype "passive"))
      (node (ref "R21") (pin "1") (pinfunction "1_1") (pintype "passive"))
      (node (ref "R22") (pin "1") (pinfunction "1_1") (pintype "passive"))
      (node (ref "R32") (pin "1") (pinfunction "1_1") (pintype "passive"))
      (node (ref "R33") (pin "1") (pinfunction "1_1") (pintype "passive"))
      (node (ref "R34") (pin "1") (pinfunction "1_1") (pintype "passive"))
      (node (ref "R35") (pin "2") (pinfunction "2_2") (pintype "passive"))
      (node (ref "R37") (pin "2") (pinfunction "2_2") (pintype "passive"))
      (node (ref "R39") (pin "2") (pinfunction "2_2") (pintype "passive"))
      (node (ref "R4") (pin "1") (pinfunction "1_1") (pintype "passive"))
      (node (ref "R41") (pin "2") (pinfunction "2_2") (pintype "passive"))
      (node (ref "R46") (pin "2") (pinfunction "2_2") (pintype "passive"))
      (node (ref "R48") (pin "2") (pinfunction "2_2") (pintype "passive"))
      (node (ref "R50") (pin "2") (pinfunction "2_2") (pintype "passive"))
      (node (ref "R51") (pin "2") (pinfunction "2_2") (pintype "passive"))
      (node (ref "R53") (pin "1") (pinfunction "1_1") (pintype "passive"))
      (node (ref "R54") (pin "2") (pinfunction "2_2") (pintype "passive"))
      (node (ref "U1") (pin "1") (pinfunction "TEMP_1") (pintype "passive"))
      (node (ref "U1") (pin "3") (pinfunction "GND_3") (pintype "passive"))
      (node (ref "U2") (pin "25") (pinfunction "EP_25") (pintype "passive"))
      (node (ref "U3") (pin "1") (pinfunction "ADJ/GND_1") (pintype "passive"))
      (node (ref "U4") (pin "1") (pinfunction "ADJ/GND_1") (pintype "passive"))
      (node (ref "U5") (pin "10") (pinfunction "GND_10") (pintype "passive"))
      (node (ref "U5") (pin "26") (pinfunction "GND_26") (pintype "passive"))
      (node (ref "U5") (pin "28") (pinfunction "GND_28") (pintype "passive"))
      (node (ref "U6") (pin "4") (pinfunction "GND_4") (pintype "passive"))
      (node (ref "U7") (pin "12") (pinfunction "VSSQ_12") (pintype "passive"))
      (node (ref "U7") (pin "28") (pinfunction "VSS_28") (pintype "passive"))
      (node (ref "U7") (pin "41") (pinfunction "VSS_41") (pintype "passive"))
      (node (ref "U7") (pin "46") (pinfunction "VSSQ_46") (pintype "passive"))
      (node (ref "U7") (pin "52") (pinfunction "VSSQ_52") (pintype "passive"))
      (node (ref "U7") (pin "54") (pinfunction "VSS_54") (pintype "passive"))
      (node (ref "U7") (pin "6") (pinfunction "VSSQ_6") (pintype "passive"))
      (node (ref "U8") (pin "102") (pinfunction "VSS_102") (pintype "passive"))
      (node (ref "U8") (pin "113") (pinfunction "VSS_113") (pintype "passive"))
      (node (ref "U8") (pin "126") (pinfunction "VSS_126") (pintype "passive"))
      (node (ref "U8") (pin "135") (pinfunction "VSS_135") (pintype "passive"))
      (node (ref "U8") (pin "14") (pinfunction "VSS_14") (pintype "passive"))
      (node (ref "U8") (pin "148") (pinfunction "VSS_148") (pintype "passive"))
      (node (ref "U8") (pin "158") (pinfunction "VSS_158") (pintype "passive"))
      (node (ref "U8") (pin "22") (pinfunction "VSS_22") (pintype "passive"))
      (node (ref "U8") (pin "37") (pinfunction "VSSA_37") (pintype "passive"))
      (node (ref "U8") (pin "61") (pinfunction "VSS_61") (pintype "passive"))
      (node (ref "U8") (pin "71") (pinfunction "VSS_71") (pintype "passive"))
      (node (ref "U8") (pin "90") (pinfunction "VSS_90") (pintype "passive"))
      (node (ref "USB1") (pin "A12") (pinfunction "GND_A12") (pintype "passive"))
      (node (ref "USB1") (pin "B12") (pinfunction "GND_B12") (pintype "passive"))
      (node (ref "X1") (pin "2") (pinfunction "GND_2") (pintype "passive"))
      (node (ref "X1") (pin "4") (pinfunction "GND_4") (pintype "passive"))
      (node (ref "X2") (pin "2") (pinfunction "GND_2") (pintype "passive"))
      (node (ref "X2") (pin "4") (pinfunction "GND_4") (pintype "passive"))
    )
    (net (code "116") (name "Net-(B1-Pad2)") (class "Default")
      (node (ref "B1") (pin "2") (pinfunction "2_2") (pintype "passive"))
      (node (ref "D11") (pin "2") (pinfunction "A_2") (pintype "passive"))
    )
    (net (code "117") (name "Net-(D1-A)") (class "Default")
      (node (ref "D1") (pin "2") (pinfunction "A_2") (pintype "passive"))
      (node (ref "R2") (pin "2") (pinfunction "2_2") (pintype "passive"))
    )
    (net (code "118") (name "Net-(D2-A)") (class "Default")
      (node (ref "D2") (pin "2") (pinfunction "A_2") (pintype "passive"))
      (node (ref "R3") (pin "2") (pinfunction "2_2") (pintype "passive"))
    )
    (net (code "119") (name "Net-(D3-K)") (class "Default")
      (node (ref "D3") (pin "1") (pinfunction "K_1") (pintype "passive"))
      (node (ref "R5") (pin "2") (pinfunction "2_2") (pintype "passive"))
    )
    (net (code "120") (name "Net-(D4-A)") (class "Default")
      (node (ref "D4") (pin "1") (pinfunction "A_1") (pintype "passive"))
      (node (ref "Q2") (pin "2") (pinfunction "S_2") (pintype "passive"))
    )
    (net (code "121") (name "Net-(D5-K)") (class "Default")
      (node (ref "D5") (pin "1") (pinfunction "K_1") (pintype "passive"))
      (node (ref "R8") (pin "2") (pinfunction "2_2") (pintype "passive"))
    )
    (net (code "122") (name "Net-(D6-A)") (class "Default")
      (node (ref "D6") (pin "2") (pinfunction "A_2") (pintype "passive"))
      (node (ref "R29") (pin "2") (pinfunction "2_2") (pintype "passive"))
    )
    (net (code "123") (name "Net-(D6-K)") (class "Default")
      (node (ref "D6") (pin "1") (pinfunction "K_1") (pintype "passive"))
      (node (ref "D7") (pin "1") (pinfunction "K_1") (pintype "passive"))
      (node (ref "J3") (pin "1") (pinfunction "1_1") (pintype "passive"))
    )
    (net (code "124") (name "Net-(D8-A)") (class "Default")
      (node (ref "D8") (pin "2") (pinfunction "A_2") (pintype "passive"))
      (node (ref "U5") (pin "22") (pinfunction "LINK-STATUS_22") (pintype "passive"))
    )
    (net (code "125") (name "Net-(D8-K)") (class "Default")
      (node (ref "D8") (pin "1") (pinfunction "K_1") (pintype "passive"))
      (node (ref "R35") (pin "1") (pinfunction "1_1") (pintype "passive"))
    )
    (net (code "126") (name "Net-(D9-A)") (class "Default")
      (node (ref "D9") (pin "2") (pinfunction "A_2") (pintype "passive"))
      (node (ref "U5") (pin "21") (pinfunction "WORK-STATUS_21") (pintype "passive"))
    )
    (net (code "127") (name "Net-(D9-K)") (class "Default")
      (node (ref "D9") (pin "1") (pinfunction "K_1") (pintype "passive"))
      (node (ref "R37") (pin "1") (pinfunction "1_1") (pintype "passive"))
    )
    (net (code "128") (name "Net-(D10-A)") (class "Default")
      (node (ref "D10") (pin "2") (pinfunction "A_2") (pintype "passive"))
      (node (ref "R49") (pin "2") (pinfunction "2_2") (pintype "passive"))
    )
    (net (code "129") (name "Net-(D11-K)") (class "Default")
      (node (ref "C29") (pin "1") (pinfunction "1_1") (pintype "passive"))
      (node (ref "D11") (pin "3") (pinfunction "K_3") (pintype "passive"))
      (node (ref "U8") (pin "6") (pinfunction "VBAT_6") (pintype "passive"))
    )
    (net (code "130") (name "Net-(J2-Pad2)") (class "Default")
      (node (ref "J2") (pin "2") (pinfunction "2_2") (pintype "passive"))
      (node (ref "R22") (pin "2") (pinfunction "2_2") (pintype "passive"))
    )
    (net (code "131") (name "Net-(J2-Pad13)") (class "Default")
      (node (ref "J2") (pin "13") (pinfunction "13_13") (pintype "passive"))
      (node (ref "R32") (pin "2") (pinfunction "2_2") (pintype "passive"))
    )
    (net (code "132") (name "Net-(J4-Pad1)") (class "Default")
      (node (ref "J4") (pin "1") (pinfunction "1_1") (pintype "passive"))
      (node (ref "R38") (pin "1") (pinfunction "1_1") (pintype "passive"))
    )
    (net (code "133") (name "Net-(J7-Pad1)") (class "Default")
      (node (ref "J7") (pin "1") (pinfunction "1_1") (pintype "passive"))
      (node (ref "R44") (pin "1") (pinfunction "1_1") (pintype "passive"))
    )
    (net (code "134") (name "Net-(J8-Pad1)") (class "Default")
      (node (ref "J8") (pin "1") (pinfunction "1_1") (pintype "passive"))
      (node (ref "R47") (pin "1") (pinfunction "1_1") (pintype "passive"))
    )
    (net (code "135") (name "Net-(Q2-G)") (class "Default")
      (node (ref "Q2") (pin "1") (pinfunction "G_1") (pintype "passive"))
      (node (ref "Q4") (pin "3") (pinfunction "C_3") (pintype "passive"))
    )
    (net (code "136") (name "Net-(Q3-B)") (class "Default")
      (node (ref "Q3") (pin "1") (pinfunction "B_1") (pintype "passive"))
      (node (ref "R12") (pin "1") (pinfunction "1_1") (pintype "passive"))
      (node (ref "R16") (pin "2") (pinfunction "2_2") (pintype "passive"))
    )
    (net (code "137") (name "Net-(Q3-C)") (class "Default")
      (node (ref "Q3") (pin "3") (pinfunction "C_3") (pintype "passive"))
      (node (ref "Q5") (pin "1") (pinfunction "G_1") (pintype "passive"))
    )
    (net (code "138") (name "Net-(Q4-B)") (class "Default")
      (node (ref "Q4") (pin "1") (pinfunction "B_1") (pintype "passive"))
      (node (ref "R15") (pin "2") (pinfunction "2_2") (pintype "passive"))
      (node (ref "R20") (pin "2") (pinfunction "2_2") (pintype "passive"))
    )
    (net (code "139") (name "Net-(Q5-D)") (class "Default")
      (node (ref "Q5") (pin "3") (pinfunction "D_3") (pintype "passive"))
      (node (ref "U3") (pin "3") (pinfunction "VIN_3") (pintype "passive"))
    )
    (net (code "140") (name "Net-(Q6-D)") (class "Default")
      (node (ref "Q6") (pin "3") (pinfunction "D_3") (pintype "passive"))
      (node (ref "U4") (pin "3") (pinfunction "VIN_3") (pintype "passive"))
    )
    (net (code "141") (name "Net-(Q6-G)") (class "Default")
      (node (ref "Q6") (pin "1") (pinfunction "G_1") (pintype "passive"))
      (node (ref "Q7") (pin "3") (pinfunction "C_3") (pintype "passive"))
      (node (ref "Q8") (pin "3") (pinfunction "C_3") (pintype "passive"))
      (node (ref "R25") (pin "1") (pinfunction "1_1") (pintype "passive"))
      (node (ref "R29") (pin "1") (pinfunction "1_1") (pintype "passive"))
    )
    (net (code "142") (name "Net-(Q7-B)") (class "Default")
      (node (ref "Q7") (pin "1") (pinfunction "B_1") (pintype "passive"))
      (node (ref "R24") (pin "1") (pinfunction "1_1") (pintype "passive"))
      (node (ref "R26") (pin "2") (pinfunction "2_2") (pintype "passive"))
    )
    (net (code "143") (name "Net-(Q8-B)") (class "Default")
      (node (ref "Q8") (pin "1") (pinfunction "B_1") (pintype "passive"))
      (node (ref "R31") (pin "2") (pinfunction "2_2") (pintype "passive"))
      (node (ref "R34") (pin "2") (pinfunction "2_2") (pintype "passive"))
    )
    (net (code "144") (name "Net-(Q9-B)") (class "Default")
      (node (ref "Q9") (pin "1") (pinfunction "B_1") (pintype "passive"))
      (node (ref "R40") (pin "1") (pinfunction "1_1") (pintype "passive"))
      (node (ref "R41") (pin "1") (pinfunction "1_1") (pintype "passive"))
    )
    (net (code "145") (name "Net-(Q9-C)") (class "Default")
      (node (ref "J5") (pin "1") (pinfunction "1_1") (pintype "passive"))
      (node (ref "Q9") (pin "3") (pinfunction "C_3") (pintype "passive"))
    )
    (net (code "146") (name "Net-(U1-CE)") (class "Default")
      (node (ref "C4") (pin "1") (pinfunction "1_1") (pintype "passive"))
      (node (ref "C5") (pin "1") (pinfunction "1_1") (pintype "passive"))
      (node (ref "R18") (pin "2") (pinfunction "2_2") (pintype "passive"))
      (node (ref "U1") (pin "4") (pinfunction "VCC_4") (pintype "passive"))
      (node (ref "U1") (pin "8") (pinfunction "CE_8") (pintype "passive"))
    )
    (net (code "147") (name "Net-(U1-CHRG#)") (class "Default")
      (node (ref "R5") (pin "1") (pinfunction "1_1") (pintype "passive"))
      (node (ref "U1") (pin "7") (pinfunction "CHRG#_7") (pintype "passive"))
    )
    (net (code "148") (name "Net-(U1-PROG)") (class "Default")
      (node (ref "R4") (pin "2") (pinfunction "2_2") (pintype "passive"))
      (node (ref "U1") (pin "2") (pinfunction "PROG_2") (pintype "passive"))
    )
    (net (code "149") (name "Net-(U1-STDBY#)") (class "Default")
      (node (ref "R8") (pin "1") (pinfunction "1_1") (pintype "passive"))
      (node (ref "U1") (pin "6") (pinfunction "STDBY#_6") (pintype "passive"))
    )
    (net (code "150") (name "Net-(U2-MDIO)") (class "Default")
      (node (ref "R6") (pin "2") (pinfunction "2_2") (pintype "passive"))
      (node (ref "U2") (pin "12") (pinfunction "MDIO_12") (pintype "passive"))
    )
    (net (code "151") (name "Net-(U2-RBIAS)") (class "Default")
      (node (ref "R21") (pin "2") (pinfunction "2_2") (pintype "passive"))
      (node (ref "U2") (pin "24") (pinfunction "RBIAS_24") (pintype "passive"))
    )
    (net (code "152") (name "Net-(U2-VDDCR)") (class "Default")
      (node (ref "C12") (pin "2") (pinfunction "2_2") (pintype "passive"))
      (node (ref "C13") (pin "2") (pinfunction "2_2") (pintype "passive"))
      (node (ref "U2") (pin "6") (pinfunction "VDDCR_6") (pintype "passive"))
    )
    (net (code "153") (name "Net-(U2-XTAL1{slash}CLKIN)") (class "Default")
      (node (ref "C19") (pin "1") (pinfunction "1_1") (pintype "passive"))
      (node (ref "U2") (pin "5") (pinfunction "XTAL1/CLKIN_5") (pintype "passive"))
      (node (ref "X1") (pin "3") (pinfunction "OSC2_3") (pintype "passive"))
    )
    (net (code "154") (name "Net-(U2-XTAL2)") (class "Default")
      (node (ref "C18") (pin "1") (pinfunction "1_1") (pintype "passive"))
      (node (ref "U2") (pin "4") (pinfunction "XTAL2_4") (pintype "passive"))
      (node (ref "X1") (pin "1") (pinfunction "OSC1_1") (pintype "passive"))
    )
    (net (code "155") (name "Net-(U8B-BYPASS_REG)") (class "Default")
      (node (ref "R54") (pin "1") (pinfunction "1_1") (pintype "passive"))
      (node (ref "U8") (pin "48") (pinfunction "BYPASS_REG_48") (pintype "passive"))
    )
    (net (code "156") (name "Net-(U8B-NRST)") (class "Default")
      (node (ref "R55") (pin "1") (pinfunction "1_1") (pintype "passive"))
      (node (ref "U8") (pin "31") (pinfunction "NRST_31") (pintype "passive"))
    )
    (net (code "157") (name "Net-(U8B-VCAP_1)") (class "Default")
      (node (ref "C45") (pin "1") (pinfunction "1_1") (pintype "passive"))
      (node (ref "U8") (pin "81") (pinfunction "VCAP_1_81") (pintype "passive"))
    )
    (net (code "158") (name "Net-(U8B-VCAP_2)") (class "Default")
      (node (ref "C54") (pin "1") (pinfunction "1_1") (pintype "passive"))
      (node (ref "U8") (pin "125") (pinfunction "VCAP_2_125") (pintype "passive"))
    )
    (net (code "159") (name "Net-(U8C-VDDA)") (class "Default")
      (node (ref "C53") (pin "2") (pinfunction "2_2") (pintype "passive"))
      (node (ref "L2") (pin "2") (pinfunction "2_2") (pintype "passive"))
      (node (ref "U8") (pin "38") (pinfunction "VREF+_38") (pintype "passive"))
      (node (ref "U8") (pin "39") (pinfunction "VDDA_39") (pintype "passive"))
    )
    (net (code "160") (name "Net-(USB1-CC1)") (class "Default")
      (node (ref "R10") (pin "2") (pinfunction "2_2") (pintype "passive"))
      (node (ref "USB1") (pin "A5") (pinfunction "CC1_A5") (pintype "passive"))
    )
    (net (code "161") (name "Net-(USB1-CC2)") (class "Default")
      (node (ref "R13") (pin "2") (pinfunction "2_2") (pintype "passive"))
      (node (ref "USB1") (pin "B5") (pinfunction "CC2_B5") (pintype "passive"))
    )
    (net (code "162") (name "SGND") (class "Default")
      (node (ref "M1") (pin "1") (pinfunction "1_1") (pintype "passive"))
      (node (ref "USB1") (pin "7") (pinfunction "EH_7") (pintype "passive"))
    )
    (net (code "163") (name "VBUS") (class "Default")
      (node (ref "C8") (pin "2") (pinfunction "2_2") (pintype "passive"))
      (node (ref "D4") (pin "2") (pinfunction "K_2") (pintype "passive"))
      (node (ref "Q1") (pin "2") (pinfunction "S_2") (pintype "passive"))
      (node (ref "Q5") (pin "2") (pinfunction "S_2") (pintype "passive"))
      (node (ref "Q6") (pin "2") (pinfunction "S_2") (pintype "passive"))
      (node (ref "Q7") (pin "2") (pinfunction "E_2") (pintype "passive"))
      (node (ref "R24") (pin "2") (pinfunction "2_2") (pintype "passive"))
      (node (ref "R25") (pin "2") (pinfunction "2_2") (pintype "passive"))
    )
    (net (code "164") (name "VCCEA") (class "Default")
      (node (ref "C15") (pin "2") (pinfunction "2_2") (pintype "passive"))
      (node (ref "C16") (pin "2") (pinfunction "2_2") (pintype "passive"))
      (node (ref "C2") (pin "2") (pinfunction "2_2") (pintype "passive"))
      (node (ref "J2") (pin "5") (pinfunction "5_5") (pintype "passive"))
      (node (ref "J2") (pin "6") (pinfunction "6_6") (pintype "passive"))
      (node (ref "J2") (pin "7") (pinfunction "7_7") (pintype "passive"))
      (node (ref "L1") (pin "2") (pinfunction "2_2") (pintype "passive"))
      (node (ref "R14") (pin "2") (pinfunction "2_2") (pintype "passive"))
      (node (ref "R17") (pin "2") (pinfunction "2_2") (pintype "passive"))
      (node (ref "R7") (pin "2") (pinfunction "2_2") (pintype "passive"))
      (node (ref "R9") (pin "2") (pinfunction "2_2") (pintype "passive"))
      (node (ref "U2") (pin "1") (pinfunction "VDD2A_1") (pintype "passive"))
      (node (ref "U2") (pin "19") (pinfunction "VDD1A_19") (pintype "passive"))
    )
    (net (code "165") (name "VCCM") (class "Default")
      (node (ref "C10") (pin "1") (pinfunction "1_1") (pintype "passive"))
      (node (ref "C11") (pin "1") (pinfunction "1_1") (pintype "passive"))
      (node (ref "C17") (pin "1") (pinfunction "1_1") (pintype "passive"))
      (node (ref "C30") (pin "2") (pinfunction "2_2") (pintype "passive"))
      (node (ref "C31") (pin "2") (pinfunction "2_2") (pintype "passive"))
      (node (ref "C32") (pin "2") (pinfunction "2_2") (pintype "passive"))
      (node (ref "C33") (pin "2") (pinfunction "2_2") (pintype "passive"))
      (node (ref "C34") (pin "2") (pinfunction "2_2") (pintype "passive"))
      (node (ref "C35") (pin "2") (pinfunction "2_2") (pintype "passive"))
      (node (ref "C36") (pin "2") (pinfunction "2_2") (pintype "passive"))
      (node (ref "C37") (pin "2") (pinfunction "2_2") (pintype "passive"))
      (node (ref "C38") (pin "2") (pinfunction "2_2") (pintype "passive"))
      (node (ref "C39") (pin "2") (pinfunction "2_2") (pintype "passive"))
      (node (ref "C40") (pin "2") (pinfunction "2_2") (pintype "passive"))
      (node (ref "C41") (pin "2") (pinfunction "2_2") (pintype "passive"))
      (node (ref "C42") (pin "2") (pinfunction "2_2") (pintype "passive"))
      (node (ref "C43") (pin "2") (pinfunction "2_2") (pintype "passive"))
      (node (ref "C44") (pin "2") (pinfunction "2_2") (pintype "passive"))
      (node (ref "C46") (pin "2") (pinfunction "2_2") (pintype "passive"))
      (node (ref "C47") (pin "2") (pinfunction "2_2") (pintype "passive"))
      (node (ref "C48") (pin "2") (pinfunction "2_2") (pintype "passive"))
      (node (ref "C49") (pin "2") (pinfunction "2_2") (pintype "passive"))
      (node (ref "C50") (pin "2") (pinfunction "2_2") (pintype "passive"))
      (node (ref "C51") (pin "2") (pinfunction "2_2") (pintype "passive"))
      (node (ref "C52") (pin "2") (pinfunction "2_2") (pintype "passive"))
      (node (ref "D11") (pin "1") (pinfunction "A_1") (pintype "passive"))
      (node (ref "J6") (pin "1") (pinfunction "1_1") (pintype "passive"))
      (node (ref "L2") (pin "1") (pinfunction "1_1") (pintype "passive"))
      (node (ref "R23") (pin "2") (pinfunction "2_2") (pintype "passive"))
      (node (ref "R3") (pin "1") (pinfunction "1_1") (pintype "passive"))
      (node (ref "R30") (pin "2") (pinfunction "2_2") (pintype "passive"))
      (node (ref "R45") (pin "1") (pinfunction "1_1") (pintype "passive"))
      (node (ref "R55") (pin "2") (pinfunction "2_2") (pintype "passive"))
      (node (ref "U4") (pin "2") (pinfunction "VOUT_2") (pintype "passive"))
      (node (ref "U6") (pin "3") (pinfunction "IO2_3") (pintype "passive"))
      (node (ref "U6") (pin "7") (pinfunction "IO3_7") (pintype "passive"))
      (node (ref "U6") (pin "8") (pinfunction "VCC_8") (pintype "passive"))
      (node (ref "U7") (pin "1") (pinfunction "VDD_1") (pintype "passive"))
      (node (ref "U7") (pin "14") (pinfunction "VDD_14") (pintype "passive"))
      (node (ref "U7") (pin "27") (pinfunction "VDD_27") (pintype "passive"))
      (node (ref "U7") (pin "3") (pinfunction "VDDQ_3") (pintype "passive"))
      (node (ref "U7") (pin "43") (pinfunction "VDDQ_43") (pintype "passive"))
      (node (ref "U7") (pin "49") (pinfunction "VDDQ_49") (pintype "passive"))
      (node (ref "U7") (pin "9") (pinfunction "VDDQ_9") (pintype "passive"))
      (node (ref "U8") (pin "103") (pinfunction "VDD_103") (pintype "passive"))
      (node (ref "U8") (pin "114") (pinfunction "VDD_114") (pintype "passive"))
      (node (ref "U8") (pin "127") (pinfunction "VDD_127") (pintype "passive"))
      (node (ref "U8") (pin "136") (pinfunction "VDD_136") (pintype "passive"))
      (node (ref "U8") (pin "149") (pinfunction "VDD_149") (pintype "passive"))
      (node (ref "U8") (pin "15") (pinfunction "VDD_15") (pintype "passive"))
      (node (ref "U8") (pin "159") (pinfunction "VDD_159") (pintype "passive"))
      (node (ref "U8") (pin "171") (pinfunction "PDR_ON_171") (pintype "passive"))
      (node (ref "U8") (pin "172") (pinfunction "VDD_172") (pintype "passive"))
      (node (ref "U8") (pin "23") (pinfunction "VDD_23") (pintype "passive"))
      (node (ref "U8") (pin "36") (pinfunction "VDD_36") (pintype "passive"))
      (node (ref "U8") (pin "49") (pinfunction "VDD_49") (pintype "passive"))
      (node (ref "U8") (pin "62") (pinfunction "VDD_62") (pintype "passive"))
      (node (ref "U8") (pin "72") (pinfunction "VDD_72") (pintype "passive"))
      (node (ref "U8") (pin "82") (pinfunction "VDD_82") (pintype "passive"))
      (node (ref "U8") (pin "91") (pinfunction "VDD_91") (pintype "passive"))
    )
    (net (code "166") (name "VCCP") (class "Default")
      (node (ref "C1") (pin "2") (pinfunction "2_2") (pintype "passive"))
      (node (ref "C14") (pin "2") (pinfunction "2_2") (pintype "passive"))
      (node (ref "C20") (pin "2") (pinfunction "2_2") (pintype "passive"))
      (node (ref "C21") (pin "2") (pinfunction "2_2") (pintype "passive"))
      (node (ref "C7") (pin "1") (pinfunction "1_1") (pintype "passive"))
      (node (ref "C9") (pin "1") (pinfunction "1_1") (pintype "passive"))
      (node (ref "J4") (pin "2") (pinfunction "2_2") (pintype "passive"))
      (node (ref "J5") (pin "4") (pinfunction "4_4") (pintype "passive"))
      (node (ref "J7") (pin "2") (pinfunction "2_2") (pintype "passive"))
      (node (ref "J8") (pin "2") (pinfunction "2_2") (pintype "passive"))
      (node (ref "L1") (pin "1") (pinfunction "1_1") (pintype "passive"))
      (node (ref "R2") (pin "1") (pinfunction "1_1") (pintype "passive"))
      (node (ref "R27") (pin "2") (pinfunction "2_2") (pintype "passive"))
      (node (ref "R28") (pin "2") (pinfunction "2_2") (pintype "passive"))
      (node (ref "R36") (pin "2") (pinfunction "2_2") (pintype "passive"))
      (node (ref "R49") (pin "1") (pinfunction "1_1") (pintype "passive"))
      (node (ref "U2") (pin "9") (pinfunction "VDDIO_9") (pintype "passive"))
      (node (ref "U3") (pin "2") (pinfunction "VOUT_2") (pintype "passive"))
      (node (ref "U5") (pin "9") (pinfunction "VBAT_9") (pintype "passive"))
    )
    (net (code "167") (name "VUSB") (class "Default")
      (node (ref "D3") (pin "2") (pinfunction "A_2") (pintype "passive"))
      (node (ref "D5") (pin "2") (pinfunction "A_2") (pintype "passive"))
      (node (ref "Q1") (pin "1") (pinfunction "G_1") (pintype "passive"))
      (node (ref "Q2") (pin "3") (pinfunction "D_3") (pintype "passive"))
      (node (ref "R1") (pin "1") (pinfunction "1_1") (pintype "passive"))
      (node (ref "R15") (pin "1") (pinfunction "1_1") (pintype "passive"))
      (node (ref "R18") (pin "1") (pinfunction "1_1") (pintype "passive"))
      (node (ref "USB1") (pin "A9") (pinfunction "VBUS_A9") (pintype "passive"))
      (node (ref "USB1") (pin "B9") (pinfunction "VBUS_B9") (pintype "passive"))
    )
    (net (code "168") (name "unconnected-(J3-Pad3)") (class "Default")
      (node (ref "J3") (pin "3") (pinfunction "3_3") (pintype "passive+no_connect"))
    )
    (net (code "169") (name "unconnected-(J3-Pad4)") (class "Default")
      (node (ref "J3") (pin "4") (pinfunction "4_4") (pintype "passive+no_connect"))
    )
    (net (code "170") (name "unconnected-(J4-Pad3)") (class "Default")
      (node (ref "J4") (pin "3") (pinfunction "3_3") (pintype "passive+no_connect"))
    )
    (net (code "171") (name "unconnected-(J4-Pad4)") (class "Default")
      (node (ref "J4") (pin "4") (pinfunction "4_4") (pintype "passive+no_connect"))
    )
    (net (code "172") (name "unconnected-(J5-Pad31)") (class "Default")
      (node (ref "J5") (pin "31") (pinfunction "31_31") (pintype "passive+no_connect"))
    )
    (net (code "173") (name "unconnected-(J6-Pad5)") (class "Default")
      (node (ref "J6") (pin "5") (pinfunction "5_5") (pintype "passive+no_connect"))
    )
    (net (code "174") (name "unconnected-(J7-Pad3)") (class "Default")
      (node (ref "J7") (pin "3") (pinfunction "3_3") (pintype "passive+no_connect"))
    )
    (net (code "175") (name "unconnected-(J7-Pad4)") (class "Default")
      (node (ref "J7") (pin "4") (pinfunction "4_4") (pintype "passive+no_connect"))
    )
    (net (code "176") (name "unconnected-(J8-Pad3)") (class "Default")
      (node (ref "J8") (pin "3") (pinfunction "3_3") (pintype "passive+no_connect"))
    )
    (net (code "177") (name "unconnected-(J8-Pad4)") (class "Default")
      (node (ref "J8") (pin "4") (pinfunction "4_4") (pintype "passive+no_connect"))
    )
    (net (code "178") (name "unconnected-(U1-EP-Pad9)") (class "Default")
      (node (ref "U1") (pin "9") (pinfunction "EP_9") (pintype "passive+no_connect"))
    )
    (net (code "179") (name "unconnected-(U2-RXER{slash}PHYAD0-Pad10)") (class "Default")
      (node (ref "U2") (pin "10") (pinfunction "RXER/PHYAD0_10") (pintype "passive+no_connect"))
    )
    (net (code "180") (name "unconnected-(U5-ANT-Pad27)") (class "Default")
      (node (ref "U5") (pin "27") (pinfunction "ANT_27") (pintype "passive+no_connect"))
    )
    (net (code "181") (name "unconnected-(U5-DLRX-Pad4)") (class "Default")
      (node (ref "U5") (pin "4") (pinfunction "DLRX_4") (pintype "passive+no_connect"))
    )
    (net (code "182") (name "unconnected-(U5-DLTX-Pad3)") (class "Default")
      (node (ref "U5") (pin "3") (pinfunction "DLTX_3") (pintype "passive+no_connect"))
    )
    (net (code "183") (name "unconnected-(U5-NC-Pad5)") (class "Default")
      (node (ref "U5") (pin "5") (pinfunction "NC_5") (pintype "passive+no_connect"))
    )
    (net (code "184") (name "unconnected-(U5-NC-Pad6)") (class "Default")
      (node (ref "U5") (pin "6") (pinfunction "NC_6") (pintype "passive+no_connect"))
    )
    (net (code "185") (name "unconnected-(U5-NC-Pad7)") (class "Default")
      (node (ref "U5") (pin "7") (pinfunction "NC_7") (pintype "passive+no_connect"))
    )
    (net (code "186") (name "unconnected-(U5-NC-Pad20)") (class "Default")
      (node (ref "U5") (pin "20") (pinfunction "NC_20") (pintype "passive+no_connect"))
    )
    (net (code "187") (name "unconnected-(U5-P07-Pad23)") (class "Default")
      (node (ref "U5") (pin "23") (pinfunction "P07_23") (pintype "passive+no_connect"))
    )
    (net (code "188") (name "unconnected-(U5-P08-Pad24)") (class "Default")
      (node (ref "U5") (pin "24") (pinfunction "P08_24") (pintype "passive+no_connect"))
    )
    (net (code "189") (name "unconnected-(U5-P09-Pad25)") (class "Default")
      (node (ref "U5") (pin "25") (pinfunction "P09_25") (pintype "passive+no_connect"))
    )
    (net (code "190") (name "unconnected-(U5-P14-Pad17)") (class "Default")
      (node (ref "U5") (pin "17") (pinfunction "P14_17") (pintype "passive+no_connect"))
    )
    (net (code "191") (name "unconnected-(U5-P15-Pad19)") (class "Default")
      (node (ref "U5") (pin "19") (pinfunction "P15_19") (pintype "passive+no_connect"))
    )
    (net (code "192") (name "unconnected-(U5-P19-Pad18)") (class "Default")
      (node (ref "U5") (pin "18") (pinfunction "P19_18") (pintype "passive+no_connect"))
    )
    (net (code "193") (name "unconnected-(U5-P20-Pad12)") (class "Default")
      (node (ref "U5") (pin "12") (pinfunction "P20_12") (pintype "passive+no_connect"))
    )
    (net (code "194") (name "unconnected-(U5-P21-Pad13)") (class "Default")
      (node (ref "U5") (pin "13") (pinfunction "P21_13") (pintype "passive+no_connect"))
    )
    (net (code "195") (name "unconnected-(U5-P22-Pad14)") (class "Default")
      (node (ref "U5") (pin "14") (pinfunction "P22_14") (pintype "passive+no_connect"))
    )
    (net (code "196") (name "unconnected-(U5-P23-Pad15)") (class "Default")
      (node (ref "U5") (pin "15") (pinfunction "P23_15") (pintype "passive+no_connect"))
    )
    (net (code "197") (name "unconnected-(U5-P24-Pad16)") (class "Default")
      (node (ref "U5") (pin "16") (pinfunction "P24_16") (pintype "passive+no_connect"))
    )
    (net (code "198") (name "unconnected-(U5-P28-Pad11)") (class "Default")
      (node (ref "U5") (pin "11") (pinfunction "P28_11") (pintype "passive+no_connect"))
    )
    (net (code "199") (name "unconnected-(U7-NC-Pad40)") (class "Default")
      (node (ref "U7") (pin "40") (pinfunction "NC_40") (pintype "passive"))
    )
    (net (code "200") (name "unconnected-(U8A-PA0{slash}WK_UP{slash}TIM2_CH1{slash}TIM2_ETR{slash}TIM5_CH1{slash}TIM8_ETR{slash}U2_CTS{slash}U4_TX{slash}ETH_MII_CRS{slash}ADC123_IN0-Pad40)") (class "Default")
      (node (ref "U8") (pin "40") (pinfunction "PA0/WK_UP/TIM2_CH1/TIM2_ETR/TIM5_CH1/TIM8_ETR/U2_CTS/U4_TX/ETH_MII_CRS/ADC123_IN0_40") (pintype "passive"))
    )
    (net (code "201") (name "unconnected-(U8A-PA8{slash}MCO1{slash}TIM1_CH1{slash}I2C3_SCL{slash}U1_CK{slash}OTG_FS_SOF{slash}LCD_R6-Pad119)") (class "Default")
      (node (ref "U8") (pin "119") (pinfunction "PA8/MCO1/TIM1_CH1/I2C3_SCL/U1_CK/OTG_FS_SOF/LCD_R6_119") (pintype "passive"))
    )
    (net (code "202") (name "unconnected-(U8A-PA11{slash}TIM1_CH4{slash}U1_CTS{slash}CAN1_RX{slash}LCD_R4{slash}OTG_FS_DM-Pad122)") (class "Default")
      (node (ref "U8") (pin "122") (pinfunction "PA11/TIM1_CH4/U1_CTS/CAN1_RX/LCD_R4/OTG_FS_DM_122") (pintype "passive"))
    )
    (net (code "203") (name "unconnected-(U8A-PA12{slash}TIM1_ETR{slash}U1_RTS{slash}CAN1_TX{slash}LCD_R5{slash}OTG_FS_DP-Pad123)") (class "Default")
      (node (ref "U8") (pin "123") (pinfunction "PA12/TIM1_ETR/U1_RTS/CAN1_TX/LCD_R5/OTG_FS_DP_123") (pintype "passive"))
    )
    (net (code "204") (name "unconnected-(U8A-PA15{slash}JTDI{slash}TIM2_CH1{slash}TIM2_ETR{slash}SPI1_NSS{slash}SPI3_NSS{slash}I2S3_WS-Pad138)") (class "Default")
      (node (ref "U8") (pin "138") (pinfunction "PA15/JTDI/TIM2_CH1/TIM2_ETR/SPI1_NSS/SPI3_NSS/I2S3_WS_138") (pintype "passive"))
    )
    (net (code "205") (name "unconnected-(U8A-PB0{slash}TIM1_CH2N{slash}TIM3_CH3{slash}TIM8_CH2N{slash}LCD_R3{slash}OTG_HS_ULPI_D1{slash}ETH_MII_RXD2{slash}ADC12_IN8-Pad56)") (class "Default")
      (node (ref "U8") (pin "56") (pinfunction "PB0/TIM1_CH2N/TIM3_CH3/TIM8_CH2N/LCD_R3/OTG_HS_ULPI_D1/ETH_MII_RXD2/ADC12_IN8_56") (pintype "passive"))
    )
    (net (code "206") (name "unconnected-(U8A-PB3{slash}JTDO{slash}TIM2_CH2{slash}SPI1_SCK{slash}SPI3_SCK{slash}I2S3_CK-Pad161)") (class "Default")
      (node (ref "U8") (pin "161") (pinfunction "PB3/JTDO/TIM2_CH2/SPI1_SCK/SPI3_SCK/I2S3_CK_161") (pintype "passive"))
    )
    (net (code "207") (name "unconnected-(U8A-PB4{slash}NJTRST{slash}TIM3_CH1{slash}SPI1_MISO{slash}SPI3_MISO{slash}I2S3ext_SD-Pad162)") (class "Default")
      (node (ref "U8") (pin "162") (pinfunction "PB4/NJTRST/TIM3_CH1/SPI1_MISO/SPI3_MISO/I2S3ext_SD_162") (pintype "passive"))
    )
    (net (code "208") (name "unconnected-(U8A-PB5{slash}TIM3_CH2{slash}I2C1_SMBA{slash}SPI1_MOSI{slash}SPI3_MOSI{slash}I2S3_SD{slash}CAN2_RX{slash}OTG_HS_ULPI_D7{slash}ETH_PPS_OUT{slash}FMC_SDCKE1{slash}DCMI_D10-Pad163)") (class "Default")
      (node (ref "U8") (pin "163") (pinfunction "PB5/TIM3_CH2/I2C1_SMBA/SPI1_MOSI/SPI3_MOSI/I2S3_SD/CAN2_RX/OTG_HS_ULPI_D7/ETH_PPS_OUT/FMC_SDCKE1/DCMI_D10_163") (pintype "passive"))
    )
    (net (code "209") (name "unconnected-(U8A-PB10{slash}TIM2_CH3{slash}I2C2_SCL{slash}SPI2_SCK{slash}I2S2_CK{slash}U3_TX{slash}OTG_HS_ULPI_D3{slash}ETH_MII_RX_ER{slash}LCD_G4-Pad79)") (class "Default")
      (node (ref "U8") (pin "79") (pinfunction "PB10/TIM2_CH3/I2C2_SCL/SPI2_SCK/I2S2_CK/U3_TX/OTG_HS_ULPI_D3/ETH_MII_RX_ER/LCD_G4_79") (pintype "passive"))
    )
    (net (code "210") (name "unconnected-(U8A-PB13{slash}TIM1_CH1N{slash}SPI2_SCK{slash}I2S2_CK{slash}U3_CTS{slash}CAN2_TX{slash}OTG_HS_ULPI_D6{slash}ETH_MII_TXD1{slash}ETH_RMII_TXD1{slash}OTG_HS_VBUS-Pad93)") (class "Default")
      (node (ref "U8") (pin "93") (pinfunction "PB13/TIM1_CH1N/SPI2_SCK/I2S2_CK/U3_CTS/CAN2_TX/OTG_HS_ULPI_D6/ETH_MII_TXD1/ETH_RMII_TXD1/OTG_HS_VBUS_93") (pintype "passive"))
    )
    (net (code "211") (name "unconnected-(U8A-PB14{slash}TIM1_CH2N{slash}TIM8_CH2N{slash}SPI2_MISO{slash}I2S2ext_SD{slash}U3_RTS{slash}TIM12_CH1{slash}OTG_HS_DM-Pad94)") (class "Default")
      (node (ref "U8") (pin "94") (pinfunction "PB14/TIM1_CH2N/TIM8_CH2N/SPI2_MISO/I2S2ext_SD/U3_RTS/TIM12_CH1/OTG_HS_DM_94") (pintype "passive"))
    )
    (net (code "212") (name "unconnected-(U8A-PB15{slash}RTC_REFIN{slash}TIM1_CH3N{slash}TIM8_CH3N{slash}SPI2_MOSI{slash}I2S2_SD{slash}TIM12_CH2{slash}OTG_HS_DP-Pad95)") (class "Default")
      (node (ref "U8") (pin "95") (pinfunction "PB15/RTC_REFIN/TIM1_CH3N/TIM8_CH3N/SPI2_MOSI/I2S2_SD/TIM12_CH2/OTG_HS_DP_95") (pintype "passive"))
    )
    (net (code "213") (name "unconnected-(U8A-PC8{slash}TIM3_CH3{slash}TIM8_CH3{slash}U6_CK{slash}SDIO_D0{slash}DCMI_D2-Pad117)") (class "Default")
      (node (ref "U8") (pin "117") (pinfunction "PC8/TIM3_CH3/TIM8_CH3/U6_CK/SDIO_D0/DCMI_D2_117") (pintype "passive"))
    )
    (net (code "214") (name "unconnected-(U8A-PC9{slash}MCO2{slash}TIM3_CH4{slash}TIM8_CH4{slash}I2C3_SDA{slash}I2S_CKIN{slash}SDIO_D1{slash}DCMI_D3-Pad118)") (class "Default")
      (node (ref "U8") (pin "118") (pinfunction "PC9/MCO2/TIM3_CH4/TIM8_CH4/I2C3_SDA/I2S_CKIN/SDIO_D1/DCMI_D3_118") (pintype "passive"))
    )
    (net (code "215") (name "unconnected-(U8A-PC12{slash}SPI3_MOSI{slash}I2S3_SD{slash}U3_CK{slash}U5_TX{slash}SDIO_CK{slash}DCMI_D9-Pad141)") (class "Default")
      (node (ref "U8") (pin "141") (pinfunction "PC12/SPI3_MOSI/I2S3_SD/U3_CK/U5_TX/SDIO_CK/DCMI_D9_141") (pintype "passive"))
    )
    (net (code "216") (name "unconnected-(U8A-PD2{slash}TIM3_ETR{slash}U5_RX{slash}SDIO_CMD{slash}DCMI_D11-Pad144)") (class "Default")
      (node (ref "U8") (pin "144") (pinfunction "PD2/TIM3_ETR/U5_RX/SDIO_CMD/DCMI_D11_144") (pintype "passive"))
    )
    (net (code "217") (name "unconnected-(U8A-PD3{slash}SPI2_SCK{slash}I2S2_CK{slash}U2_CTS{slash}FMC_CLK{slash}DCMI_D5{slash}LCD_G7-Pad145)") (class "Default")
      (node (ref "U8") (pin "145") (pinfunction "PD3/SPI2_SCK/I2S2_CK/U2_CTS/FMC_CLK/DCMI_D5/LCD_G7_145") (pintype "passive"))
    )
    (net (code "218") (name "unconnected-(U8A-PD4{slash}U2_RTS{slash}FMC_NOE-Pad146)") (class "Default")
      (node (ref "U8") (pin "146") (pinfunction "PD4/U2_RTS/FMC_NOE_146") (pintype "passive"))
    )
    (net (code "219") (name "unconnected-(U8A-PD5{slash}U2_TX{slash}FMC_NWE-Pad147)") (class "Default")
      (node (ref "U8") (pin "147") (pinfunction "PD5/U2_TX/FMC_NWE_147") (pintype "passive"))
    )
    (net (code "220") (name "unconnected-(U8A-PD6{slash}SPI3_MOSI{slash}I2S3_SD{slash}SAI1_SD_A{slash}U2_RX{slash}FMC_NWAIT{slash}DCMI_D10{slash}LCD_B2-Pad150)") (class "Default")
      (node (ref "U8") (pin "150") (pinfunction "PD6/SPI3_MOSI/I2S3_SD/SAI1_SD_A/U2_RX/FMC_NWAIT/DCMI_D10/LCD_B2_150") (pintype "passive"))
    )
    (net (code "221") (name "unconnected-(U8A-PD7{slash}U2_CK{slash}FMC_NE1{slash}FMC_NCE2-Pad151)") (class "Default")
      (node (ref "U8") (pin "151") (pinfunction "PD7/U2_CK/FMC_NE1/FMC_NCE2_151") (pintype "passive"))
    )
    (net (code "222") (name "unconnected-(U8A-PD12{slash}TIM4_CH1{slash}U3_RTS{slash}FMC_A17-Pad100)") (class "Default")
      (node (ref "U8") (pin "100") (pinfunction "PD12/TIM4_CH1/U3_RTS/FMC_A17_100") (pintype "passive"))
    )
    (net (code "223") (name "unconnected-(U8A-PD13{slash}TIM4_CH2{slash}FMC_A18-Pad101)") (class "Default")
      (node (ref "U8") (pin "101") (pinfunction "PD13/TIM4_CH2/FMC_A18_101") (pintype "passive"))
    )
    (net (code "224") (name "unconnected-(U8A-PE2{slash}SPI4_SCK{slash}SAI1_MCLK_A{slash}ETH_MII_TXD3{slash}FMC_A23-Pad1)") (class "Default")
      (node (ref "U8") (pin "1") (pinfunction "PE2/SPI4_SCK/SAI1_MCLK_A/ETH_MII_TXD3/FMC_A23_1") (pintype "passive"))
    )
    (net (code "225") (name "unconnected-(U8A-PE3{slash}SAI1_SD_B{slash}FMC_A19-Pad2)") (class "Default")
      (node (ref "U8") (pin "2") (pinfunction "PE3/SAI1_SD_B/FMC_A19_2") (pintype "passive"))
    )
    (net (code "226") (name "unconnected-(U8B-PG3{slash}FMC_A13-Pad107)") (class "Default")
      (node (ref "U8") (pin "107") (pinfunction "PG3/FMC_A13_107") (pintype "passive"))
    )
    (net (code "227") (name "unconnected-(U8B-PG9{slash}U6_RX{slash}FMC_NE2{slash}FMC_NCE3-Pad152)") (class "Default")
      (node (ref "U8") (pin "152") (pinfunction "PG9/U6_RX/FMC_NE2/FMC_NCE3_152") (pintype "passive"))
    )
    (net (code "228") (name "unconnected-(U8B-PH4{slash}I2C2_SCL{slash}OTG_HS_ULPI_NXT-Pad45)") (class "Default")
      (node (ref "U8") (pin "45") (pinfunction "PH4/I2C2_SCL/OTG_HS_ULPI_NXT_45") (pintype "passive"))
    )
    (net (code "229") (name "unconnected-(U8B-PH5{slash}I2C2_SDA{slash}SPI5_NSS{slash}FMC_SDNWE-Pad46)") (class "Default")
      (node (ref "U8") (pin "46") (pinfunction "PH5/I2C2_SDA/SPI5_NSS/FMC_SDNWE_46") (pintype "passive"))
    )
    (net (code "230") (name "unconnected-(U8B-PH6{slash}I2C2_SMBA{slash}SPI5_SCK{slash}TIM12_CH1{slash}ETH_MII_RXD2{slash}FMC_SDNE1{slash}DCMI_D8-Pad83)") (class "Default")
      (node (ref "U8") (pin "83") (pinfunction "PH6/I2C2_SMBA/SPI5_SCK/TIM12_CH1/ETH_MII_RXD2/FMC_SDNE1/DCMI_D8_83") (pintype "passive"))
    )
    (net (code "231") (name "unconnected-(U8B-PH7{slash}I2C3_SCL{slash}SPI5_MISO{slash}ETH_MII_RXD3{slash}FMC_SDCKE1{slash}DCMI_D9-Pad84)") (class "Default")
      (node (ref "U8") (pin "84") (pinfunction "PH7/I2C3_SCL/SPI5_MISO/ETH_MII_RXD3/FMC_SDCKE1/DCMI_D9_84") (pintype "passive"))
    )
    (net (code "232") (name "unconnected-(U8B-PI3{slash}TIM8_ETR{slash}SPI2_MOSI{slash}I2S2_SD{slash}FMC_D27{slash}DCMI_D10-Pad134)") (class "Default")
      (node (ref "U8") (pin "134") (pinfunction "PI3/TIM8_ETR/SPI2_MOSI/I2S2_SD/FMC_D27/DCMI_D10_134") (pintype "passive"))
    )
    (net (code "233") (name "unconnected-(U8B-PI8{slash}TAMP_2-Pad7)") (class "Default")
      (node (ref "U8") (pin "7") (pinfunction "PI8/TAMP_2_7") (pintype "passive"))
    )
    (net (code "234") (name "unconnected-(U8B-PI11{slash}OTG_HS_ULPI_DIR-Pad13)") (class "Default")
      (node (ref "U8") (pin "13") (pinfunction "PI11/OTG_HS_ULPI_DIR_13") (pintype "passive"))
    )
  )
)
